# Server_CPU_Power.net
KiCad netlist of a schematic drawn in Altium Designer
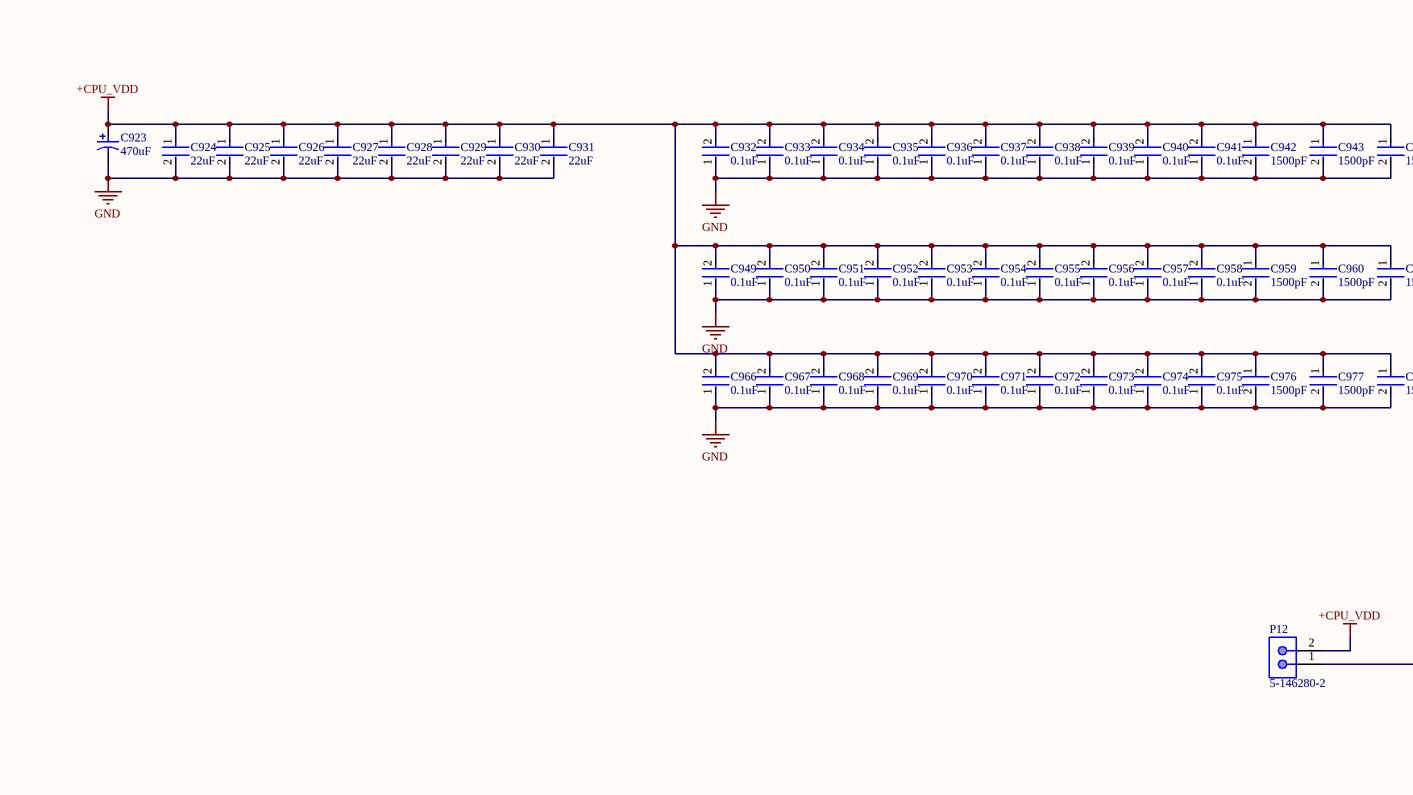
[diagram p0: Server_CPU_Power.SchDoc, top left]
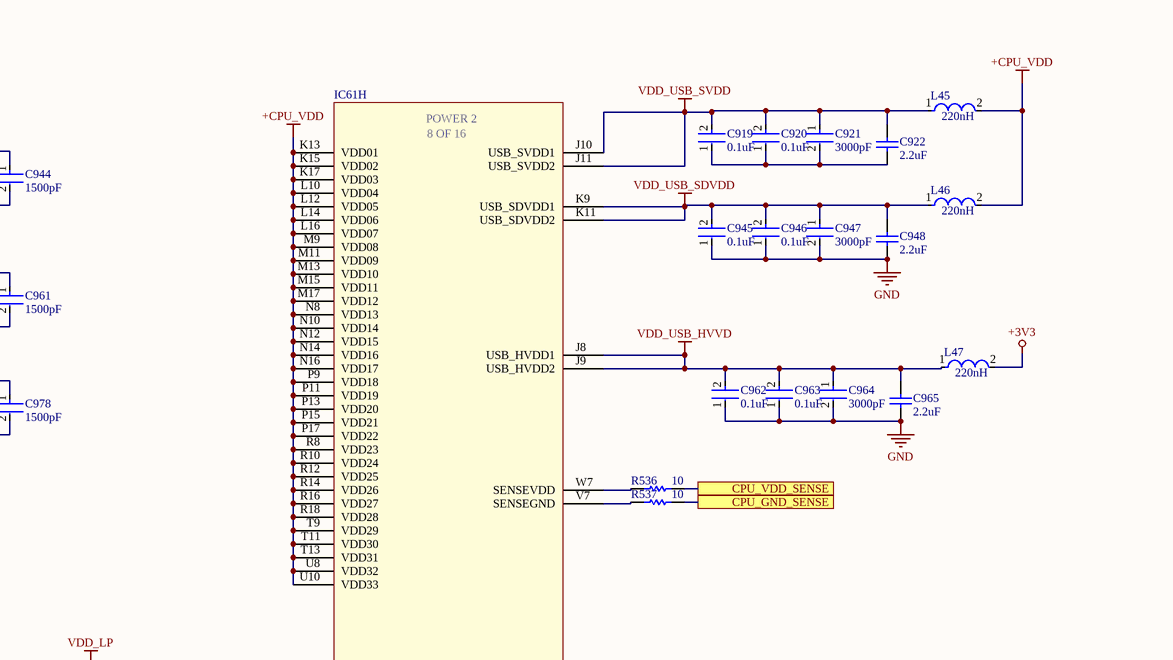
[diagram p1: Server_CPU_Power.SchDoc, top right]
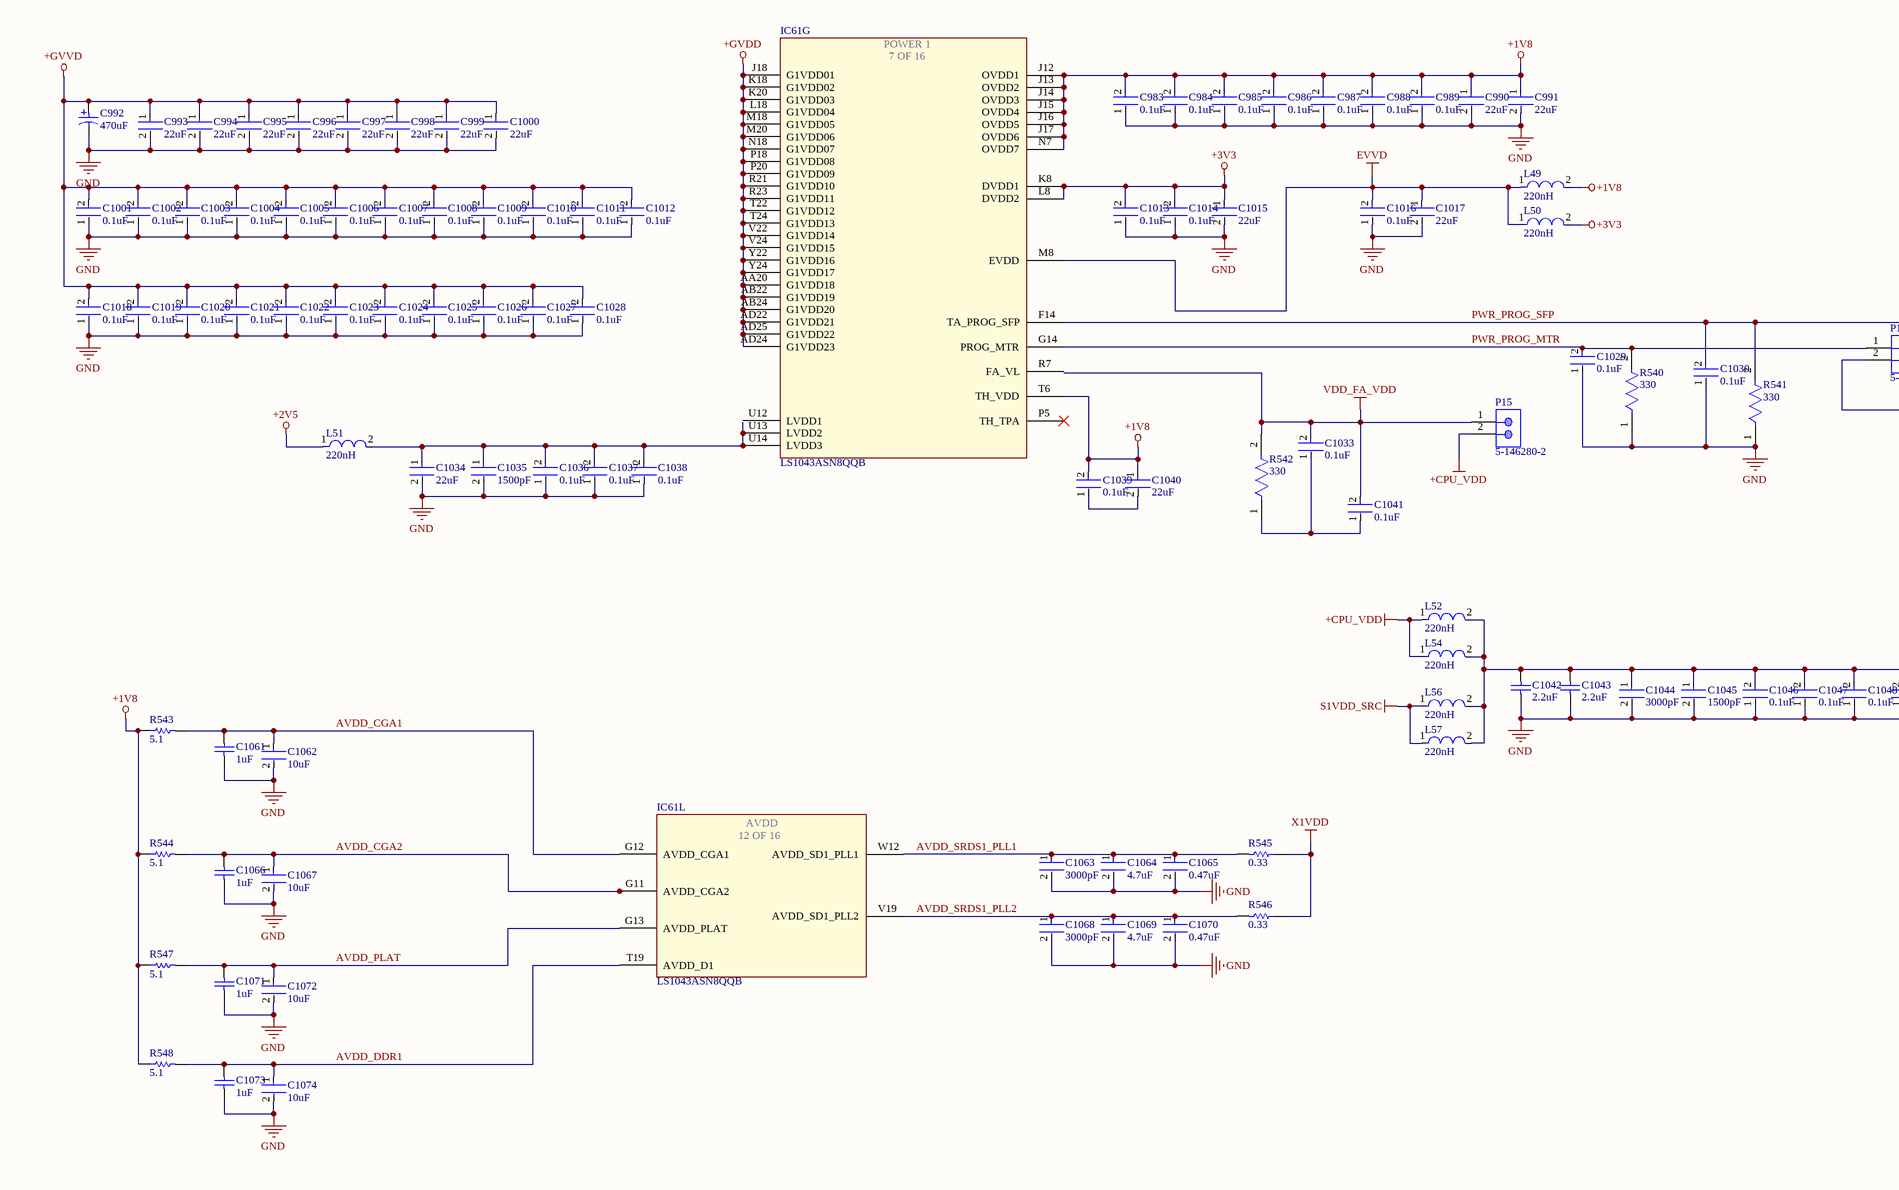
[diagram p2: Server_CPU_Power.SchDoc, bottom left]
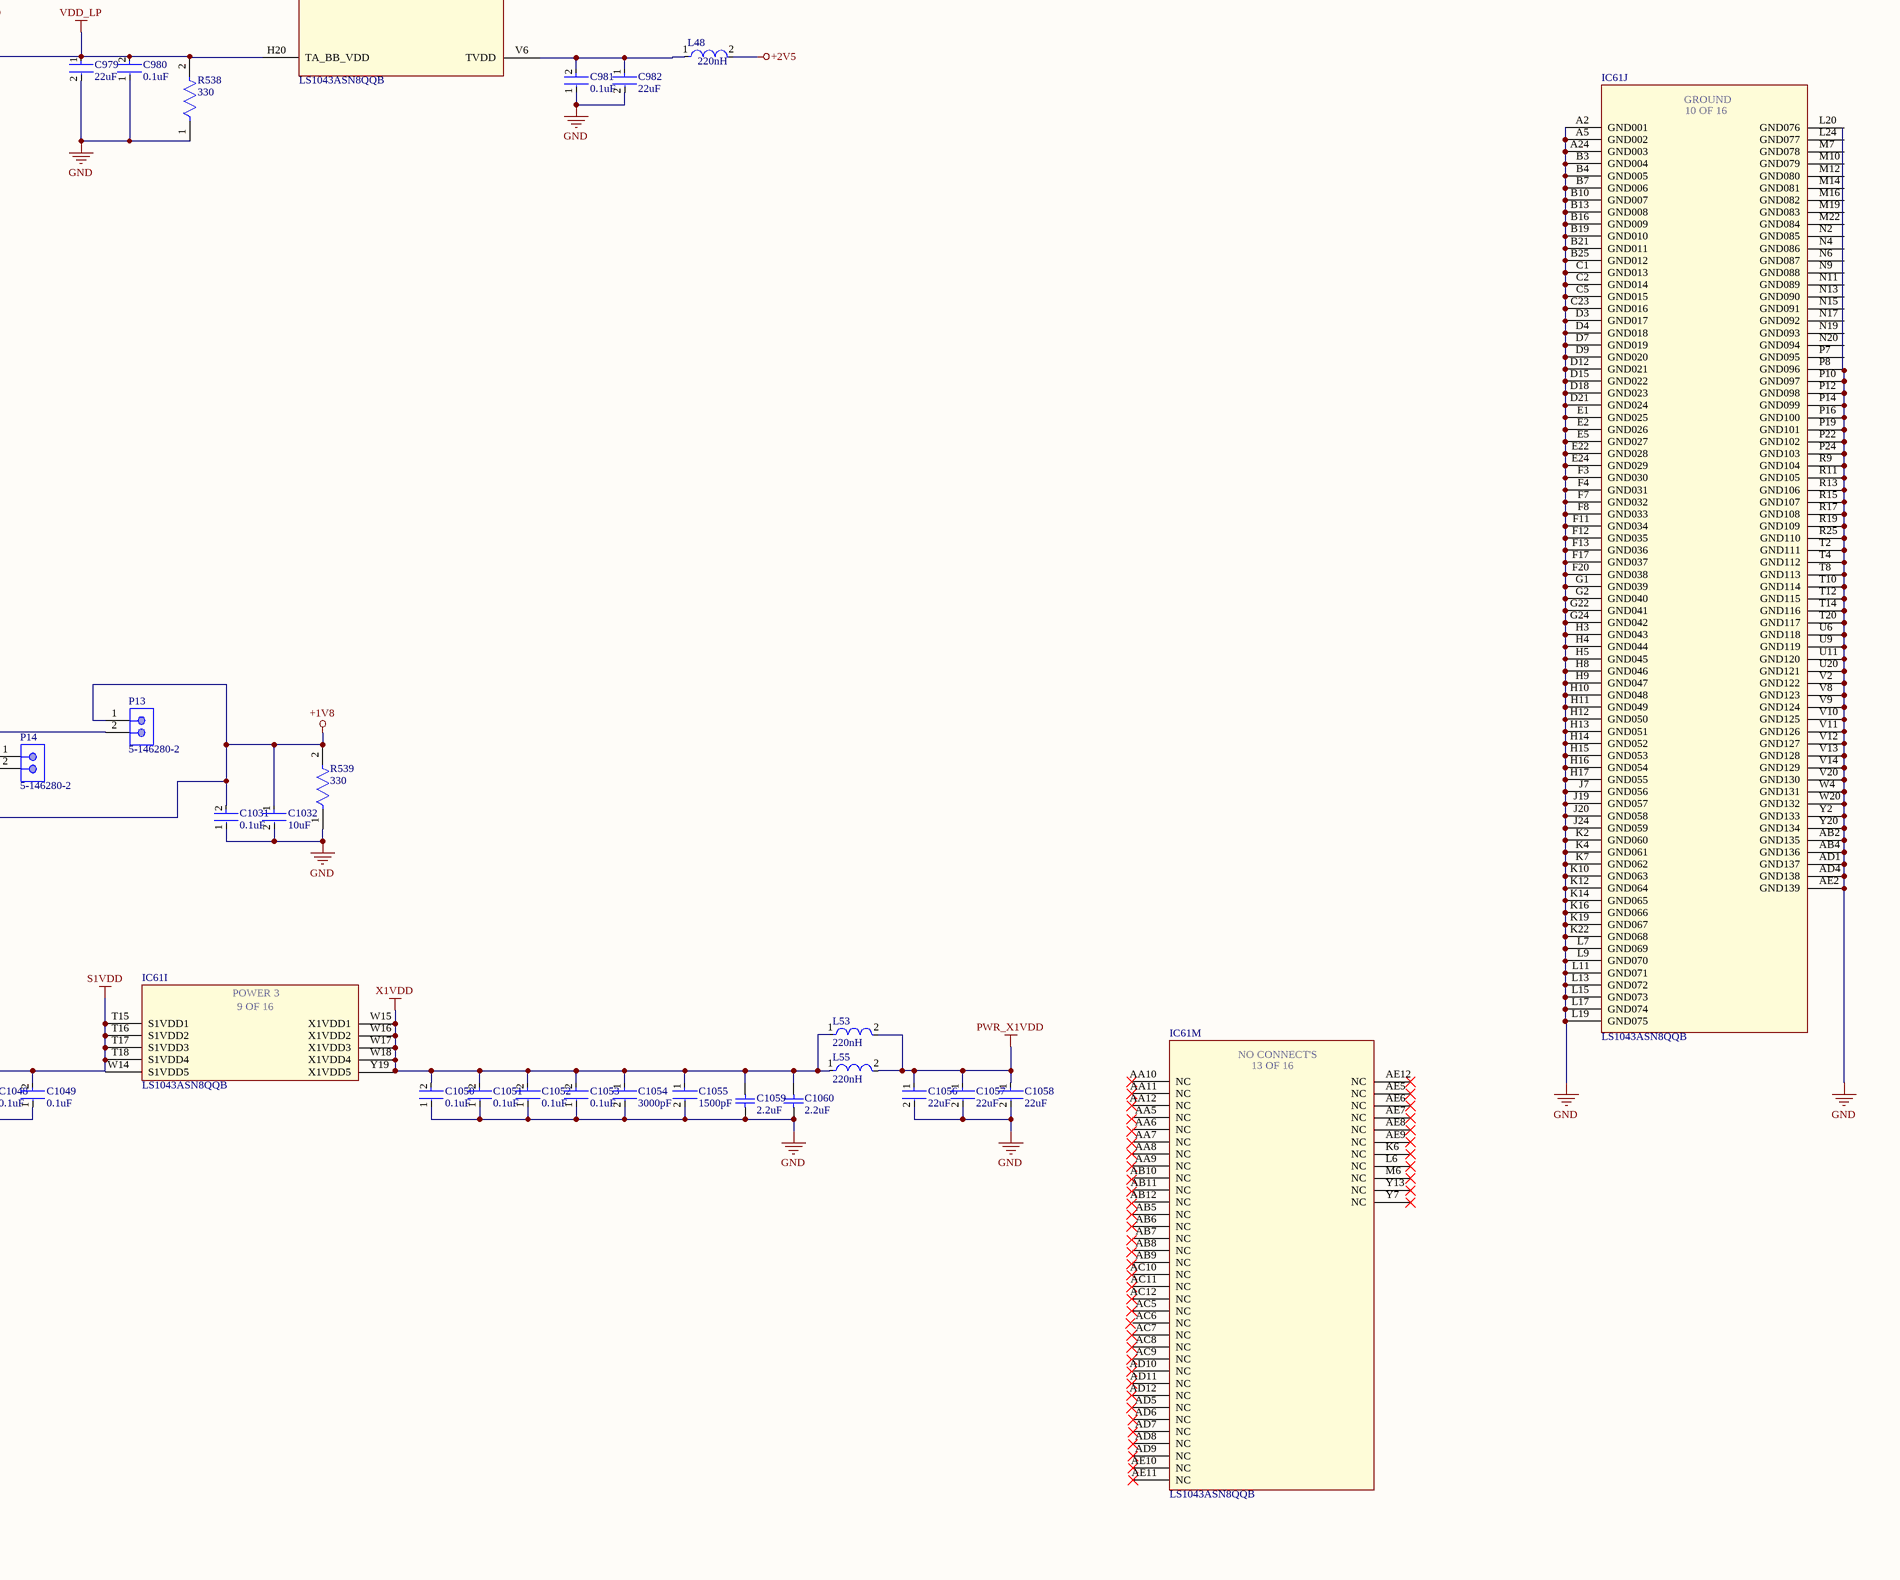
[diagram p3: Server_CPU_Power.SchDoc, bottom right]

(export (version "E")
  (design (tool "Eeschema 10.0.6"))
  (components
    (comp (ref "C919")
      (value "0.1uF")
      (footprint "FP-GRM15-MFG")
      (description "CAP CER 0.1UF 16V X7R 0402")
      (fields (field (name "MANUFACTURER PART NUMBER") "GRM155R71C104KA88D") (field (name "TOLERANCE") "10%"))
      (libsource (lib "Altium Content Vault") (part "236180d848d6139a670b325ea6854c9"))
    )
    (comp (ref "C920")
      (value "0.1uF")
      (footprint "FP-GRM15-MFG")
      (description "CAP CER 0.1UF 16V X7R 0402")
      (fields (field (name "MANUFACTURER PART NUMBER") "GRM155R71C104KA88D") (field (name "TOLERANCE") "10%"))
      (libsource (lib "Altium Content Vault") (part "236180d848d6139a670b325ea6854c9"))
    )
    (comp (ref "C921")
      (value "3000pF")
      (footprint "FP-GRM155-0_05-IPC_B")
      (description "Chip Multilayer Ceramic Capacitors for General Purpose, 0402, 3000pF, U2J, -750ppm/°C, 5%, 10V")
      (fields (field (name "TOLERANCE") "5%"))
      (libsource (lib "Altium Content Vault") (part "02cd4be3c70576c341d710602a673aa"))
    )
    (comp (ref "C922")
      (value "2.2uF")
      (footprint "CAPC1005X55X30NL05T10")
      (fields (field (name "MANUFACTURER") "Kemet") (field (name "PART NUMBER") "C0402C225M9PACTU"))
      (libsource (lib "Altium Content Vault") (part "CAP"))
    )
    (comp (ref "C923")
      (value "470uF")
      (footprint "PNSC-FK-V-F_V")
      (fields (field (name "MANUFACTURER") "Panasonic"))
      (libsource (lib "Altium Content Vault") (part "CAP-P-2"))
    )
    (comp (ref "C924")
      (value "22uF")
      (footprint "FP-GRM21B-0_15-MFG")
      (description "Chip Multilayer Ceramic Capacitors for General Purpose, 0805, 22uF, X5R, 15%, 20%, 6.3V")
      (fields (field (name "VOLTAGE") "6.3V") (field (name "TOLERANCE") "20%"))
      (libsource (lib "Altium Content Vault") (part "b4654b650e69147ec39a6b967a45e02"))
    )
    (comp (ref "C925")
      (value "22uF")
      (footprint "FP-GRM21B-0_15-MFG")
      (description "Chip Multilayer Ceramic Capacitors for General Purpose, 0805, 22uF, X5R, 15%, 20%, 6.3V")
      (fields (field (name "VOLTAGE") "6.3V") (field (name "TOLERANCE") "20%"))
      (libsource (lib "Altium Content Vault") (part "b4654b650e69147ec39a6b967a45e02"))
    )
    (comp (ref "C926")
      (value "22uF")
      (footprint "FP-GRM21B-0_15-MFG")
      (description "Chip Multilayer Ceramic Capacitors for General Purpose, 0805, 22uF, X5R, 15%, 20%, 6.3V")
      (fields (field (name "VOLTAGE") "6.3V") (field (name "TOLERANCE") "20%"))
      (libsource (lib "Altium Content Vault") (part "b4654b650e69147ec39a6b967a45e02"))
    )
    (comp (ref "C927")
      (value "22uF")
      (footprint "FP-GRM21B-0_15-MFG")
      (description "Chip Multilayer Ceramic Capacitors for General Purpose, 0805, 22uF, X5R, 15%, 20%, 6.3V")
      (fields (field (name "VOLTAGE") "6.3V") (field (name "TOLERANCE") "20%"))
      (libsource (lib "Altium Content Vault") (part "b4654b650e69147ec39a6b967a45e02"))
    )
    (comp (ref "C928")
      (value "22uF")
      (footprint "FP-GRM21B-0_15-MFG")
      (description "Chip Multilayer Ceramic Capacitors for General Purpose, 0805, 22uF, X5R, 15%, 20%, 6.3V")
      (fields (field (name "VOLTAGE") "6.3V") (field (name "TOLERANCE") "20%"))
      (libsource (lib "Altium Content Vault") (part "b4654b650e69147ec39a6b967a45e02"))
    )
    (comp (ref "C929")
      (value "22uF")
      (footprint "FP-GRM21B-0_15-MFG")
      (description "Chip Multilayer Ceramic Capacitors for General Purpose, 0805, 22uF, X5R, 15%, 20%, 6.3V")
      (fields (field (name "VOLTAGE") "6.3V") (field (name "TOLERANCE") "20%"))
      (libsource (lib "Altium Content Vault") (part "b4654b650e69147ec39a6b967a45e02"))
    )
    (comp (ref "C930")
      (value "22uF")
      (footprint "FP-GRM21B-0_15-MFG")
      (description "Chip Multilayer Ceramic Capacitors for General Purpose, 0805, 22uF, X5R, 15%, 20%, 6.3V")
      (fields (field (name "VOLTAGE") "6.3V") (field (name "TOLERANCE") "20%"))
      (libsource (lib "Altium Content Vault") (part "b4654b650e69147ec39a6b967a45e02"))
    )
    (comp (ref "C931")
      (value "22uF")
      (footprint "FP-GRM21B-0_15-MFG")
      (description "Chip Multilayer Ceramic Capacitors for General Purpose, 0805, 22uF, X5R, 15%, 20%, 6.3V")
      (fields (field (name "VOLTAGE") "6.3V") (field (name "TOLERANCE") "20%"))
      (libsource (lib "Altium Content Vault") (part "b4654b650e69147ec39a6b967a45e02"))
    )
    (comp (ref "C932")
      (value "0.1uF")
      (footprint "FP-GRM15-MFG")
      (description "CAP CER 0.1UF 16V X7R 0402")
      (fields (field (name "MANUFACTURER PART NUMBER") "GRM155R71C104KA88D") (field (name "TOLERANCE") "10%"))
      (libsource (lib "Altium Content Vault") (part "236180d848d6139a670b325ea6854c9"))
    )
    (comp (ref "C933")
      (value "0.1uF")
      (footprint "FP-GRM15-MFG")
      (description "CAP CER 0.1UF 16V X7R 0402")
      (fields (field (name "MANUFACTURER PART NUMBER") "GRM155R71C104KA88D") (field (name "TOLERANCE") "10%"))
      (libsource (lib "Altium Content Vault") (part "236180d848d6139a670b325ea6854c9"))
    )
    (comp (ref "C934")
      (value "0.1uF")
      (footprint "FP-GRM15-MFG")
      (description "CAP CER 0.1UF 16V X7R 0402")
      (fields (field (name "MANUFACTURER PART NUMBER") "GRM155R71C104KA88D") (field (name "TOLERANCE") "10%"))
      (libsource (lib "Altium Content Vault") (part "236180d848d6139a670b325ea6854c9"))
    )
    (comp (ref "C935")
      (value "0.1uF")
      (footprint "FP-GRM15-MFG")
      (description "CAP CER 0.1UF 16V X7R 0402")
      (fields (field (name "MANUFACTURER PART NUMBER") "GRM155R71C104KA88D") (field (name "TOLERANCE") "10%"))
      (libsource (lib "Altium Content Vault") (part "236180d848d6139a670b325ea6854c9"))
    )
    (comp (ref "C936")
      (value "0.1uF")
      (footprint "FP-GRM15-MFG")
      (description "CAP CER 0.1UF 16V X7R 0402")
      (fields (field (name "MANUFACTURER PART NUMBER") "GRM155R71C104KA88D") (field (name "TOLERANCE") "10%"))
      (libsource (lib "Altium Content Vault") (part "236180d848d6139a670b325ea6854c9"))
    )
    (comp (ref "C937")
      (value "0.1uF")
      (footprint "FP-GRM15-MFG")
      (description "CAP CER 0.1UF 16V X7R 0402")
      (fields (field (name "MANUFACTURER PART NUMBER") "GRM155R71C104KA88D") (field (name "TOLERANCE") "10%"))
      (libsource (lib "Altium Content Vault") (part "236180d848d6139a670b325ea6854c9"))
    )
    (comp (ref "C938")
      (value "0.1uF")
      (footprint "FP-GRM15-MFG")
      (description "CAP CER 0.1UF 16V X7R 0402")
      (fields (field (name "MANUFACTURER PART NUMBER") "GRM155R71C104KA88D") (field (name "TOLERANCE") "10%"))
      (libsource (lib "Altium Content Vault") (part "236180d848d6139a670b325ea6854c9"))
    )
    (comp (ref "C939")
      (value "0.1uF")
      (footprint "FP-GRM15-MFG")
      (description "CAP CER 0.1UF 16V X7R 0402")
      (fields (field (name "MANUFACTURER PART NUMBER") "GRM155R71C104KA88D") (field (name "TOLERANCE") "10%"))
      (libsource (lib "Altium Content Vault") (part "236180d848d6139a670b325ea6854c9"))
    )
    (comp (ref "C940")
      (value "0.1uF")
      (footprint "FP-GRM15-MFG")
      (description "CAP CER 0.1UF 16V X7R 0402")
      (fields (field (name "MANUFACTURER PART NUMBER") "GRM155R71C104KA88D") (field (name "TOLERANCE") "10%"))
      (libsource (lib "Altium Content Vault") (part "236180d848d6139a670b325ea6854c9"))
    )
    (comp (ref "C941")
      (value "0.1uF")
      (footprint "FP-GRM15-MFG")
      (description "CAP CER 0.1UF 16V X7R 0402")
      (fields (field (name "MANUFACTURER PART NUMBER") "GRM155R71C104KA88D") (field (name "TOLERANCE") "10%"))
      (libsource (lib "Altium Content Vault") (part "236180d848d6139a670b325ea6854c9"))
    )
    (comp (ref "C942")
      (value "1500pF")
      (footprint "FP-C0402-BB-MFG")
      (description "CAP CER 1500PF 50V X7R 0402")
      (fields
        (field (name "OCTOPART") "https://octopart.com/c0402c152k5ractu-kemet-125298")
        (field (name "TOLERANCE") "0.1")
      )
      (libsource (lib "Altium Content Vault") (part "b4654b650e69147ec39a6b967a45e02"))
    )
    (comp (ref "C943")
      (value "1500pF")
      (footprint "FP-C0402-BB-MFG")
      (description "CAP CER 1500PF 50V X7R 0402")
      (fields
        (field (name "OCTOPART") "https://octopart.com/c0402c152k5ractu-kemet-125298")
        (field (name "TOLERANCE") "0.1")
      )
      (libsource (lib "Altium Content Vault") (part "b4654b650e69147ec39a6b967a45e02"))
    )
    (comp (ref "C944")
      (value "1500pF")
      (footprint "FP-C0402-BB-MFG")
      (description "CAP CER 1500PF 50V X7R 0402")
      (fields
        (field (name "OCTOPART") "https://octopart.com/c0402c152k5ractu-kemet-125298")
        (field (name "TOLERANCE") "0.1")
      )
      (libsource (lib "Altium Content Vault") (part "b4654b650e69147ec39a6b967a45e02"))
    )
    (comp (ref "C945")
      (value "0.1uF")
      (footprint "FP-GRM15-MFG")
      (description "CAP CER 0.1UF 16V X7R 0402")
      (fields (field (name "MANUFACTURER PART NUMBER") "GRM155R71C104KA88D") (field (name "TOLERANCE") "10%"))
      (libsource (lib "Altium Content Vault") (part "236180d848d6139a670b325ea6854c9"))
    )
    (comp (ref "C946")
      (value "0.1uF")
      (footprint "FP-GRM15-MFG")
      (description "CAP CER 0.1UF 16V X7R 0402")
      (fields (field (name "MANUFACTURER PART NUMBER") "GRM155R71C104KA88D") (field (name "TOLERANCE") "10%"))
      (libsource (lib "Altium Content Vault") (part "236180d848d6139a670b325ea6854c9"))
    )
    (comp (ref "C947")
      (value "3000pF")
      (footprint "FP-GRM155-0_05-IPC_B")
      (description "Chip Multilayer Ceramic Capacitors for General Purpose, 0402, 3000pF, U2J, -750ppm/°C, 5%, 10V")
      (fields (field (name "TOLERANCE") "5%"))
      (libsource (lib "Altium Content Vault") (part "02cd4be3c70576c341d710602a673aa"))
    )
    (comp (ref "C948")
      (value "2.2uF")
      (footprint "CAPC1005X55X30NL05T10")
      (fields (field (name "MANUFACTURER") "Kemet") (field (name "PART NUMBER") "C0402C225M9PACTU"))
      (libsource (lib "Altium Content Vault") (part "CAP"))
    )
    (comp (ref "C949")
      (value "0.1uF")
      (footprint "FP-GRM15-MFG")
      (description "CAP CER 0.1UF 16V X7R 0402")
      (fields (field (name "MANUFACTURER PART NUMBER") "GRM155R71C104KA88D") (field (name "TOLERANCE") "10%"))
      (libsource (lib "Altium Content Vault") (part "236180d848d6139a670b325ea6854c9"))
    )
    (comp (ref "C950")
      (value "0.1uF")
      (footprint "FP-GRM15-MFG")
      (description "CAP CER 0.1UF 16V X7R 0402")
      (fields (field (name "MANUFACTURER PART NUMBER") "GRM155R71C104KA88D") (field (name "TOLERANCE") "10%"))
      (libsource (lib "Altium Content Vault") (part "236180d848d6139a670b325ea6854c9"))
    )
    (comp (ref "C951")
      (value "0.1uF")
      (footprint "FP-GRM15-MFG")
      (description "CAP CER 0.1UF 16V X7R 0402")
      (fields (field (name "MANUFACTURER PART NUMBER") "GRM155R71C104KA88D") (field (name "TOLERANCE") "10%"))
      (libsource (lib "Altium Content Vault") (part "236180d848d6139a670b325ea6854c9"))
    )
    (comp (ref "C952")
      (value "0.1uF")
      (footprint "FP-GRM15-MFG")
      (description "CAP CER 0.1UF 16V X7R 0402")
      (fields (field (name "MANUFACTURER PART NUMBER") "GRM155R71C104KA88D") (field (name "TOLERANCE") "10%"))
      (libsource (lib "Altium Content Vault") (part "236180d848d6139a670b325ea6854c9"))
    )
    (comp (ref "C953")
      (value "0.1uF")
      (footprint "FP-GRM15-MFG")
      (description "CAP CER 0.1UF 16V X7R 0402")
      (fields (field (name "MANUFACTURER PART NUMBER") "GRM155R71C104KA88D") (field (name "TOLERANCE") "10%"))
      (libsource (lib "Altium Content Vault") (part "236180d848d6139a670b325ea6854c9"))
    )
    (comp (ref "C954")
      (value "0.1uF")
      (footprint "FP-GRM15-MFG")
      (description "CAP CER 0.1UF 16V X7R 0402")
      (fields (field (name "MANUFACTURER PART NUMBER") "GRM155R71C104KA88D") (field (name "TOLERANCE") "10%"))
      (libsource (lib "Altium Content Vault") (part "236180d848d6139a670b325ea6854c9"))
    )
    (comp (ref "C955")
      (value "0.1uF")
      (footprint "FP-GRM15-MFG")
      (description "CAP CER 0.1UF 16V X7R 0402")
      (fields (field (name "MANUFACTURER PART NUMBER") "GRM155R71C104KA88D") (field (name "TOLERANCE") "10%"))
      (libsource (lib "Altium Content Vault") (part "236180d848d6139a670b325ea6854c9"))
    )
    (comp (ref "C956")
      (value "0.1uF")
      (footprint "FP-GRM15-MFG")
      (description "CAP CER 0.1UF 16V X7R 0402")
      (fields (field (name "MANUFACTURER PART NUMBER") "GRM155R71C104KA88D") (field (name "TOLERANCE") "10%"))
      (libsource (lib "Altium Content Vault") (part "236180d848d6139a670b325ea6854c9"))
    )
    (comp (ref "C957")
      (value "0.1uF")
      (footprint "FP-GRM15-MFG")
      (description "CAP CER 0.1UF 16V X7R 0402")
      (fields (field (name "MANUFACTURER PART NUMBER") "GRM155R71C104KA88D") (field (name "TOLERANCE") "10%"))
      (libsource (lib "Altium Content Vault") (part "236180d848d6139a670b325ea6854c9"))
    )
    (comp (ref "C958")
      (value "0.1uF")
      (footprint "FP-GRM15-MFG")
      (description "CAP CER 0.1UF 16V X7R 0402")
      (fields (field (name "MANUFACTURER PART NUMBER") "GRM155R71C104KA88D") (field (name "TOLERANCE") "10%"))
      (libsource (lib "Altium Content Vault") (part "236180d848d6139a670b325ea6854c9"))
    )
    (comp (ref "C959")
      (value "1500pF")
      (footprint "FP-C0402-BB-MFG")
      (description "CAP CER 1500PF 50V X7R 0402")
      (fields
        (field (name "OCTOPART") "https://octopart.com/c0402c152k5ractu-kemet-125298")
        (field (name "TOLERANCE") "0.1")
      )
      (libsource (lib "Altium Content Vault") (part "b4654b650e69147ec39a6b967a45e02"))
    )
    (comp (ref "C960")
      (value "1500pF")
      (footprint "FP-C0402-BB-MFG")
      (description "CAP CER 1500PF 50V X7R 0402")
      (fields
        (field (name "OCTOPART") "https://octopart.com/c0402c152k5ractu-kemet-125298")
        (field (name "TOLERANCE") "0.1")
      )
      (libsource (lib "Altium Content Vault") (part "b4654b650e69147ec39a6b967a45e02"))
    )
    (comp (ref "C961")
      (value "1500pF")
      (footprint "FP-C0402-BB-MFG")
      (description "CAP CER 1500PF 50V X7R 0402")
      (fields
        (field (name "OCTOPART") "https://octopart.com/c0402c152k5ractu-kemet-125298")
        (field (name "TOLERANCE") "0.1")
      )
      (libsource (lib "Altium Content Vault") (part "b4654b650e69147ec39a6b967a45e02"))
    )
    (comp (ref "C962")
      (value "0.1uF")
      (footprint "FP-GRM15-MFG")
      (description "CAP CER 0.1UF 16V X7R 0402")
      (fields (field (name "MANUFACTURER PART NUMBER") "GRM155R71C104KA88D") (field (name "TOLERANCE") "10%"))
      (libsource (lib "Altium Content Vault") (part "236180d848d6139a670b325ea6854c9"))
    )
    (comp (ref "C963")
      (value "0.1uF")
      (footprint "FP-GRM15-MFG")
      (description "CAP CER 0.1UF 16V X7R 0402")
      (fields (field (name "MANUFACTURER PART NUMBER") "GRM155R71C104KA88D") (field (name "TOLERANCE") "10%"))
      (libsource (lib "Altium Content Vault") (part "236180d848d6139a670b325ea6854c9"))
    )
    (comp (ref "C964")
      (value "3000pF")
      (footprint "FP-GRM155-0_05-IPC_B")
      (description "Chip Multilayer Ceramic Capacitors for General Purpose, 0402, 3000pF, U2J, -750ppm/°C, 5%, 10V")
      (fields (field (name "TOLERANCE") "5%"))
      (libsource (lib "Altium Content Vault") (part "02cd4be3c70576c341d710602a673aa"))
    )
    (comp (ref "C965")
      (value "2.2uF")
      (footprint "CAPC1005X55X30NL05T10")
      (fields (field (name "MANUFACTURER") "Kemet") (field (name "PART NUMBER") "C0402C225M9PACTU"))
      (libsource (lib "Altium Content Vault") (part "CAP"))
    )
    (comp (ref "C966")
      (value "0.1uF")
      (footprint "FP-GRM15-MFG")
      (description "CAP CER 0.1UF 16V X7R 0402")
      (fields (field (name "MANUFACTURER PART NUMBER") "GRM155R71C104KA88D") (field (name "TOLERANCE") "10%"))
      (libsource (lib "Altium Content Vault") (part "236180d848d6139a670b325ea6854c9"))
    )
    (comp (ref "C967")
      (value "0.1uF")
      (footprint "FP-GRM15-MFG")
      (description "CAP CER 0.1UF 16V X7R 0402")
      (fields (field (name "MANUFACTURER PART NUMBER") "GRM155R71C104KA88D") (field (name "TOLERANCE") "10%"))
      (libsource (lib "Altium Content Vault") (part "236180d848d6139a670b325ea6854c9"))
    )
    (comp (ref "C968")
      (value "0.1uF")
      (footprint "FP-GRM15-MFG")
      (description "CAP CER 0.1UF 16V X7R 0402")
      (fields (field (name "MANUFACTURER PART NUMBER") "GRM155R71C104KA88D") (field (name "TOLERANCE") "10%"))
      (libsource (lib "Altium Content Vault") (part "236180d848d6139a670b325ea6854c9"))
    )
    (comp (ref "C969")
      (value "0.1uF")
      (footprint "FP-GRM15-MFG")
      (description "CAP CER 0.1UF 16V X7R 0402")
      (fields (field (name "MANUFACTURER PART NUMBER") "GRM155R71C104KA88D") (field (name "TOLERANCE") "10%"))
      (libsource (lib "Altium Content Vault") (part "236180d848d6139a670b325ea6854c9"))
    )
    (comp (ref "C970")
      (value "0.1uF")
      (footprint "FP-GRM15-MFG")
      (description "CAP CER 0.1UF 16V X7R 0402")
      (fields (field (name "MANUFACTURER PART NUMBER") "GRM155R71C104KA88D") (field (name "TOLERANCE") "10%"))
      (libsource (lib "Altium Content Vault") (part "236180d848d6139a670b325ea6854c9"))
    )
    (comp (ref "C971")
      (value "0.1uF")
      (footprint "FP-GRM15-MFG")
      (description "CAP CER 0.1UF 16V X7R 0402")
      (fields (field (name "MANUFACTURER PART NUMBER") "GRM155R71C104KA88D") (field (name "TOLERANCE") "10%"))
      (libsource (lib "Altium Content Vault") (part "236180d848d6139a670b325ea6854c9"))
    )
    (comp (ref "C972")
      (value "0.1uF")
      (footprint "FP-GRM15-MFG")
      (description "CAP CER 0.1UF 16V X7R 0402")
      (fields (field (name "MANUFACTURER PART NUMBER") "GRM155R71C104KA88D") (field (name "TOLERANCE") "10%"))
      (libsource (lib "Altium Content Vault") (part "236180d848d6139a670b325ea6854c9"))
    )
    (comp (ref "C973")
      (value "0.1uF")
      (footprint "FP-GRM15-MFG")
      (description "CAP CER 0.1UF 16V X7R 0402")
      (fields (field (name "MANUFACTURER PART NUMBER") "GRM155R71C104KA88D") (field (name "TOLERANCE") "10%"))
      (libsource (lib "Altium Content Vault") (part "236180d848d6139a670b325ea6854c9"))
    )
    (comp (ref "C974")
      (value "0.1uF")
      (footprint "FP-GRM15-MFG")
      (description "CAP CER 0.1UF 16V X7R 0402")
      (fields (field (name "MANUFACTURER PART NUMBER") "GRM155R71C104KA88D") (field (name "TOLERANCE") "10%"))
      (libsource (lib "Altium Content Vault") (part "236180d848d6139a670b325ea6854c9"))
    )
    (comp (ref "C975")
      (value "0.1uF")
      (footprint "FP-GRM15-MFG")
      (description "CAP CER 0.1UF 16V X7R 0402")
      (fields (field (name "MANUFACTURER PART NUMBER") "GRM155R71C104KA88D") (field (name "TOLERANCE") "10%"))
      (libsource (lib "Altium Content Vault") (part "236180d848d6139a670b325ea6854c9"))
    )
    (comp (ref "C976")
      (value "1500pF")
      (footprint "FP-C0402-BB-MFG")
      (description "CAP CER 1500PF 50V X7R 0402")
      (fields
        (field (name "OCTOPART") "https://octopart.com/c0402c152k5ractu-kemet-125298")
        (field (name "TOLERANCE") "0.1")
      )
      (libsource (lib "Altium Content Vault") (part "b4654b650e69147ec39a6b967a45e02"))
    )
    (comp (ref "C977")
      (value "1500pF")
      (footprint "FP-C0402-BB-MFG")
      (description "CAP CER 1500PF 50V X7R 0402")
      (fields
        (field (name "OCTOPART") "https://octopart.com/c0402c152k5ractu-kemet-125298")
        (field (name "TOLERANCE") "0.1")
      )
      (libsource (lib "Altium Content Vault") (part "b4654b650e69147ec39a6b967a45e02"))
    )
    (comp (ref "C978")
      (value "1500pF")
      (footprint "FP-C0402-BB-MFG")
      (description "CAP CER 1500PF 50V X7R 0402")
      (fields
        (field (name "OCTOPART") "https://octopart.com/c0402c152k5ractu-kemet-125298")
        (field (name "TOLERANCE") "0.1")
      )
      (libsource (lib "Altium Content Vault") (part "b4654b650e69147ec39a6b967a45e02"))
    )
    (comp (ref "C979")
      (value "22uF")
      (footprint "FP-GRM21B-0_15-MFG")
      (description "Chip Multilayer Ceramic Capacitors for General Purpose, 0805, 22uF, X5R, 15%, 20%, 6.3V")
      (fields (field (name "VOLTAGE") "6.3V") (field (name "TOLERANCE") "20%"))
      (libsource (lib "Altium Content Vault") (part "b4654b650e69147ec39a6b967a45e02"))
    )
    (comp (ref "C980")
      (value "0.1uF")
      (footprint "FP-GRM15-MFG")
      (description "CAP CER 0.1UF 16V X7R 0402")
      (fields (field (name "MANUFACTURER PART NUMBER") "GRM155R71C104KA88D") (field (name "TOLERANCE") "10%"))
      (libsource (lib "Altium Content Vault") (part "236180d848d6139a670b325ea6854c9"))
    )
    (comp (ref "C981")
      (value "0.1uF")
      (footprint "FP-GRM15-MFG")
      (description "CAP CER 0.1UF 16V X7R 0402")
      (fields (field (name "MANUFACTURER PART NUMBER") "GRM155R71C104KA88D") (field (name "TOLERANCE") "10%"))
      (libsource (lib "Altium Content Vault") (part "236180d848d6139a670b325ea6854c9"))
    )
    (comp (ref "C982")
      (value "22uF")
      (footprint "FP-GRM21B-0_15-MFG")
      (description "Chip Multilayer Ceramic Capacitors for General Purpose, 0805, 22uF, X5R, 15%, 20%, 6.3V")
      (fields (field (name "VOLTAGE") "6.3V") (field (name "TOLERANCE") "20%"))
      (libsource (lib "Altium Content Vault") (part "b4654b650e69147ec39a6b967a45e02"))
    )
    (comp (ref "C983")
      (value "0.1uF")
      (footprint "FP-GRM15-MFG")
      (description "CAP CER 0.1UF 16V X7R 0402")
      (fields (field (name "MANUFACTURER PART NUMBER") "GRM155R71C104KA88D") (field (name "TOLERANCE") "10%"))
      (libsource (lib "Altium Content Vault") (part "236180d848d6139a670b325ea6854c9"))
    )
    (comp (ref "C984")
      (value "0.1uF")
      (footprint "FP-GRM15-MFG")
      (description "CAP CER 0.1UF 16V X7R 0402")
      (fields (field (name "MANUFACTURER PART NUMBER") "GRM155R71C104KA88D") (field (name "TOLERANCE") "10%"))
      (libsource (lib "Altium Content Vault") (part "236180d848d6139a670b325ea6854c9"))
    )
    (comp (ref "C985")
      (value "0.1uF")
      (footprint "FP-GRM15-MFG")
      (description "CAP CER 0.1UF 16V X7R 0402")
      (fields (field (name "MANUFACTURER PART NUMBER") "GRM155R71C104KA88D") (field (name "TOLERANCE") "10%"))
      (libsource (lib "Altium Content Vault") (part "236180d848d6139a670b325ea6854c9"))
    )
    (comp (ref "C986")
      (value "0.1uF")
      (footprint "FP-GRM15-MFG")
      (description "CAP CER 0.1UF 16V X7R 0402")
      (fields (field (name "MANUFACTURER PART NUMBER") "GRM155R71C104KA88D") (field (name "TOLERANCE") "10%"))
      (libsource (lib "Altium Content Vault") (part "236180d848d6139a670b325ea6854c9"))
    )
    (comp (ref "C987")
      (value "0.1uF")
      (footprint "FP-GRM15-MFG")
      (description "CAP CER 0.1UF 16V X7R 0402")
      (fields (field (name "MANUFACTURER PART NUMBER") "GRM155R71C104KA88D") (field (name "TOLERANCE") "10%"))
      (libsource (lib "Altium Content Vault") (part "236180d848d6139a670b325ea6854c9"))
    )
    (comp (ref "C988")
      (value "0.1uF")
      (footprint "FP-GRM15-MFG")
      (description "CAP CER 0.1UF 16V X7R 0402")
      (fields (field (name "MANUFACTURER PART NUMBER") "GRM155R71C104KA88D") (field (name "TOLERANCE") "10%"))
      (libsource (lib "Altium Content Vault") (part "236180d848d6139a670b325ea6854c9"))
    )
    (comp (ref "C989")
      (value "0.1uF")
      (footprint "FP-GRM15-MFG")
      (description "CAP CER 0.1UF 16V X7R 0402")
      (fields (field (name "MANUFACTURER PART NUMBER") "GRM155R71C104KA88D") (field (name "TOLERANCE") "10%"))
      (libsource (lib "Altium Content Vault") (part "236180d848d6139a670b325ea6854c9"))
    )
    (comp (ref "C990")
      (value "22uF")
      (footprint "FP-GRM21B-0_15-MFG")
      (description "Chip Multilayer Ceramic Capacitors for General Purpose, 0805, 22uF, X5R, 15%, 20%, 6.3V")
      (fields (field (name "VOLTAGE") "6.3V") (field (name "TOLERANCE") "20%"))
      (libsource (lib "Altium Content Vault") (part "b4654b650e69147ec39a6b967a45e02"))
    )
    (comp (ref "C991")
      (value "22uF")
      (footprint "FP-GRM21B-0_15-MFG")
      (description "Chip Multilayer Ceramic Capacitors for General Purpose, 0805, 22uF, X5R, 15%, 20%, 6.3V")
      (fields (field (name "VOLTAGE") "6.3V") (field (name "TOLERANCE") "20%"))
      (libsource (lib "Altium Content Vault") (part "b4654b650e69147ec39a6b967a45e02"))
    )
    (comp (ref "C992")
      (value "470uF")
      (footprint "PNSC-FK-V-F_V")
      (fields (field (name "MANUFACTURER") "Panasonic"))
      (libsource (lib "Altium Content Vault") (part "CAP-P-2"))
    )
    (comp (ref "C993")
      (value "22uF")
      (footprint "FP-GRM21B-0_15-MFG")
      (description "Chip Multilayer Ceramic Capacitors for General Purpose, 0805, 22uF, X5R, 15%, 20%, 6.3V")
      (fields (field (name "VOLTAGE") "6.3V") (field (name "TOLERANCE") "20%"))
      (libsource (lib "Altium Content Vault") (part "b4654b650e69147ec39a6b967a45e02"))
    )
    (comp (ref "C994")
      (value "22uF")
      (footprint "FP-GRM21B-0_15-MFG")
      (description "Chip Multilayer Ceramic Capacitors for General Purpose, 0805, 22uF, X5R, 15%, 20%, 6.3V")
      (fields (field (name "VOLTAGE") "6.3V") (field (name "TOLERANCE") "20%"))
      (libsource (lib "Altium Content Vault") (part "b4654b650e69147ec39a6b967a45e02"))
    )
    (comp (ref "C995")
      (value "22uF")
      (footprint "FP-GRM21B-0_15-MFG")
      (description "Chip Multilayer Ceramic Capacitors for General Purpose, 0805, 22uF, X5R, 15%, 20%, 6.3V")
      (fields (field (name "VOLTAGE") "6.3V") (field (name "TOLERANCE") "20%"))
      (libsource (lib "Altium Content Vault") (part "b4654b650e69147ec39a6b967a45e02"))
    )
    (comp (ref "C996")
      (value "22uF")
      (footprint "FP-GRM21B-0_15-MFG")
      (description "Chip Multilayer Ceramic Capacitors for General Purpose, 0805, 22uF, X5R, 15%, 20%, 6.3V")
      (fields (field (name "VOLTAGE") "6.3V") (field (name "TOLERANCE") "20%"))
      (libsource (lib "Altium Content Vault") (part "b4654b650e69147ec39a6b967a45e02"))
    )
    (comp (ref "C997")
      (value "22uF")
      (footprint "FP-GRM21B-0_15-MFG")
      (description "Chip Multilayer Ceramic Capacitors for General Purpose, 0805, 22uF, X5R, 15%, 20%, 6.3V")
      (fields (field (name "VOLTAGE") "6.3V") (field (name "TOLERANCE") "20%"))
      (libsource (lib "Altium Content Vault") (part "b4654b650e69147ec39a6b967a45e02"))
    )
    (comp (ref "C998")
      (value "22uF")
      (footprint "FP-GRM21B-0_15-MFG")
      (description "Chip Multilayer Ceramic Capacitors for General Purpose, 0805, 22uF, X5R, 15%, 20%, 6.3V")
      (fields (field (name "VOLTAGE") "6.3V") (field (name "TOLERANCE") "20%"))
      (libsource (lib "Altium Content Vault") (part "b4654b650e69147ec39a6b967a45e02"))
    )
    (comp (ref "C999")
      (value "22uF")
      (footprint "FP-GRM21B-0_15-MFG")
      (description "Chip Multilayer Ceramic Capacitors for General Purpose, 0805, 22uF, X5R, 15%, 20%, 6.3V")
      (fields (field (name "VOLTAGE") "6.3V") (field (name "TOLERANCE") "20%"))
      (libsource (lib "Altium Content Vault") (part "b4654b650e69147ec39a6b967a45e02"))
    )
    (comp (ref "C1000")
      (value "22uF")
      (footprint "FP-GRM21B-0_15-MFG")
      (description "Chip Multilayer Ceramic Capacitors for General Purpose, 0805, 22uF, X5R, 15%, 20%, 6.3V")
      (fields (field (name "VOLTAGE") "6.3V") (field (name "TOLERANCE") "20%"))
      (libsource (lib "Altium Content Vault") (part "b4654b650e69147ec39a6b967a45e02"))
    )
    (comp (ref "C1001")
      (value "0.1uF")
      (footprint "FP-GRM15-MFG")
      (description "CAP CER 0.1UF 16V X7R 0402")
      (fields (field (name "MANUFACTURER PART NUMBER") "GRM155R71C104KA88D") (field (name "TOLERANCE") "10%"))
      (libsource (lib "Altium Content Vault") (part "236180d848d6139a670b325ea6854c9"))
    )
    (comp (ref "C1002")
      (value "0.1uF")
      (footprint "FP-GRM15-MFG")
      (description "CAP CER 0.1UF 16V X7R 0402")
      (fields (field (name "MANUFACTURER PART NUMBER") "GRM155R71C104KA88D") (field (name "TOLERANCE") "10%"))
      (libsource (lib "Altium Content Vault") (part "236180d848d6139a670b325ea6854c9"))
    )
    (comp (ref "C1003")
      (value "0.1uF")
      (footprint "FP-GRM15-MFG")
      (description "CAP CER 0.1UF 16V X7R 0402")
      (fields (field (name "MANUFACTURER PART NUMBER") "GRM155R71C104KA88D") (field (name "TOLERANCE") "10%"))
      (libsource (lib "Altium Content Vault") (part "236180d848d6139a670b325ea6854c9"))
    )
    (comp (ref "C1004")
      (value "0.1uF")
      (footprint "FP-GRM15-MFG")
      (description "CAP CER 0.1UF 16V X7R 0402")
      (fields (field (name "MANUFACTURER PART NUMBER") "GRM155R71C104KA88D") (field (name "TOLERANCE") "10%"))
      (libsource (lib "Altium Content Vault") (part "236180d848d6139a670b325ea6854c9"))
    )
    (comp (ref "C1005")
      (value "0.1uF")
      (footprint "FP-GRM15-MFG")
      (description "CAP CER 0.1UF 16V X7R 0402")
      (fields (field (name "MANUFACTURER PART NUMBER") "GRM155R71C104KA88D") (field (name "TOLERANCE") "10%"))
      (libsource (lib "Altium Content Vault") (part "236180d848d6139a670b325ea6854c9"))
    )
    (comp (ref "C1006")
      (value "0.1uF")
      (footprint "FP-GRM15-MFG")
      (description "CAP CER 0.1UF 16V X7R 0402")
      (fields (field (name "MANUFACTURER PART NUMBER") "GRM155R71C104KA88D") (field (name "TOLERANCE") "10%"))
      (libsource (lib "Altium Content Vault") (part "236180d848d6139a670b325ea6854c9"))
    )
    (comp (ref "C1007")
      (value "0.1uF")
      (footprint "FP-GRM15-MFG")
      (description "CAP CER 0.1UF 16V X7R 0402")
      (fields (field (name "MANUFACTURER PART NUMBER") "GRM155R71C104KA88D") (field (name "TOLERANCE") "10%"))
      (libsource (lib "Altium Content Vault") (part "236180d848d6139a670b325ea6854c9"))
    )
    (comp (ref "C1008")
      (value "0.1uF")
      (footprint "FP-GRM15-MFG")
      (description "CAP CER 0.1UF 16V X7R 0402")
      (fields (field (name "MANUFACTURER PART NUMBER") "GRM155R71C104KA88D") (field (name "TOLERANCE") "10%"))
      (libsource (lib "Altium Content Vault") (part "236180d848d6139a670b325ea6854c9"))
    )
    (comp (ref "C1009")
      (value "0.1uF")
      (footprint "FP-GRM15-MFG")
      (description "CAP CER 0.1UF 16V X7R 0402")
      (fields (field (name "MANUFACTURER PART NUMBER") "GRM155R71C104KA88D") (field (name "TOLERANCE") "10%"))
      (libsource (lib "Altium Content Vault") (part "236180d848d6139a670b325ea6854c9"))
    )
    (comp (ref "C1010")
      (value "0.1uF")
      (footprint "FP-GRM15-MFG")
      (description "CAP CER 0.1UF 16V X7R 0402")
      (fields (field (name "MANUFACTURER PART NUMBER") "GRM155R71C104KA88D") (field (name "TOLERANCE") "10%"))
      (libsource (lib "Altium Content Vault") (part "236180d848d6139a670b325ea6854c9"))
    )
    (comp (ref "C1011")
      (value "0.1uF")
      (footprint "FP-GRM15-MFG")
      (description "CAP CER 0.1UF 16V X7R 0402")
      (fields (field (name "MANUFACTURER PART NUMBER") "GRM155R71C104KA88D") (field (name "TOLERANCE") "10%"))
      (libsource (lib "Altium Content Vault") (part "236180d848d6139a670b325ea6854c9"))
    )
    (comp (ref "C1012")
      (value "0.1uF")
      (footprint "FP-GRM15-MFG")
      (description "CAP CER 0.1UF 16V X7R 0402")
      (fields (field (name "MANUFACTURER PART NUMBER") "GRM155R71C104KA88D") (field (name "TOLERANCE") "10%"))
      (libsource (lib "Altium Content Vault") (part "236180d848d6139a670b325ea6854c9"))
    )
    (comp (ref "C1013")
      (value "0.1uF")
      (footprint "FP-GRM15-MFG")
      (description "CAP CER 0.1UF 16V X7R 0402")
      (fields (field (name "MANUFACTURER PART NUMBER") "GRM155R71C104KA88D") (field (name "TOLERANCE") "10%"))
      (libsource (lib "Altium Content Vault") (part "236180d848d6139a670b325ea6854c9"))
    )
    (comp (ref "C1014")
      (value "0.1uF")
      (footprint "FP-GRM15-MFG")
      (description "CAP CER 0.1UF 16V X7R 0402")
      (fields (field (name "MANUFACTURER PART NUMBER") "GRM155R71C104KA88D") (field (name "TOLERANCE") "10%"))
      (libsource (lib "Altium Content Vault") (part "236180d848d6139a670b325ea6854c9"))
    )
    (comp (ref "C1015")
      (value "22uF")
      (footprint "FP-GRM21B-0_15-MFG")
      (description "Chip Multilayer Ceramic Capacitors for General Purpose, 0805, 22uF, X5R, 15%, 20%, 6.3V")
      (fields (field (name "VOLTAGE") "6.3V") (field (name "TOLERANCE") "20%"))
      (libsource (lib "Altium Content Vault") (part "b4654b650e69147ec39a6b967a45e02"))
    )
    (comp (ref "C1016")
      (value "0.1uF")
      (footprint "FP-GRM15-MFG")
      (description "CAP CER 0.1UF 16V X7R 0402")
      (fields (field (name "MANUFACTURER PART NUMBER") "GRM155R71C104KA88D") (field (name "TOLERANCE") "10%"))
      (libsource (lib "Altium Content Vault") (part "236180d848d6139a670b325ea6854c9"))
    )
    (comp (ref "C1017")
      (value "22uF")
      (footprint "FP-GRM21B-0_15-MFG")
      (description "Chip Multilayer Ceramic Capacitors for General Purpose, 0805, 22uF, X5R, 15%, 20%, 6.3V")
      (fields (field (name "VOLTAGE") "6.3V") (field (name "TOLERANCE") "20%"))
      (libsource (lib "Altium Content Vault") (part "b4654b650e69147ec39a6b967a45e02"))
    )
    (comp (ref "C1018")
      (value "0.1uF")
      (footprint "FP-GRM15-MFG")
      (description "CAP CER 0.1UF 16V X7R 0402")
      (fields (field (name "MANUFACTURER PART NUMBER") "GRM155R71C104KA88D") (field (name "TOLERANCE") "10%"))
      (libsource (lib "Altium Content Vault") (part "236180d848d6139a670b325ea6854c9"))
    )
    (comp (ref "C1019")
      (value "0.1uF")
      (footprint "FP-GRM15-MFG")
      (description "CAP CER 0.1UF 16V X7R 0402")
      (fields (field (name "MANUFACTURER PART NUMBER") "GRM155R71C104KA88D") (field (name "TOLERANCE") "10%"))
      (libsource (lib "Altium Content Vault") (part "236180d848d6139a670b325ea6854c9"))
    )
    (comp (ref "C1020")
      (value "0.1uF")
      (footprint "FP-GRM15-MFG")
      (description "CAP CER 0.1UF 16V X7R 0402")
      (fields (field (name "MANUFACTURER PART NUMBER") "GRM155R71C104KA88D") (field (name "TOLERANCE") "10%"))
      (libsource (lib "Altium Content Vault") (part "236180d848d6139a670b325ea6854c9"))
    )
    (comp (ref "C1021")
      (value "0.1uF")
      (footprint "FP-GRM15-MFG")
      (description "CAP CER 0.1UF 16V X7R 0402")
      (fields (field (name "MANUFACTURER PART NUMBER") "GRM155R71C104KA88D") (field (name "TOLERANCE") "10%"))
      (libsource (lib "Altium Content Vault") (part "236180d848d6139a670b325ea6854c9"))
    )
    (comp (ref "C1022")
      (value "0.1uF")
      (footprint "FP-GRM15-MFG")
      (description "CAP CER 0.1UF 16V X7R 0402")
      (fields (field (name "MANUFACTURER PART NUMBER") "GRM155R71C104KA88D") (field (name "TOLERANCE") "10%"))
      (libsource (lib "Altium Content Vault") (part "236180d848d6139a670b325ea6854c9"))
    )
    (comp (ref "C1023")
      (value "0.1uF")
      (footprint "FP-GRM15-MFG")
      (description "CAP CER 0.1UF 16V X7R 0402")
      (fields (field (name "MANUFACTURER PART NUMBER") "GRM155R71C104KA88D") (field (name "TOLERANCE") "10%"))
      (libsource (lib "Altium Content Vault") (part "236180d848d6139a670b325ea6854c9"))
    )
    (comp (ref "C1024")
      (value "0.1uF")
      (footprint "FP-GRM15-MFG")
      (description "CAP CER 0.1UF 16V X7R 0402")
      (fields (field (name "MANUFACTURER PART NUMBER") "GRM155R71C104KA88D") (field (name "TOLERANCE") "10%"))
      (libsource (lib "Altium Content Vault") (part "236180d848d6139a670b325ea6854c9"))
    )
    (comp (ref "C1025")
      (value "0.1uF")
      (footprint "FP-GRM15-MFG")
      (description "CAP CER 0.1UF 16V X7R 0402")
      (fields (field (name "MANUFACTURER PART NUMBER") "GRM155R71C104KA88D") (field (name "TOLERANCE") "10%"))
      (libsource (lib "Altium Content Vault") (part "236180d848d6139a670b325ea6854c9"))
    )
    (comp (ref "C1026")
      (value "0.1uF")
      (footprint "FP-GRM15-MFG")
      (description "CAP CER 0.1UF 16V X7R 0402")
      (fields (field (name "MANUFACTURER PART NUMBER") "GRM155R71C104KA88D") (field (name "TOLERANCE") "10%"))
      (libsource (lib "Altium Content Vault") (part "236180d848d6139a670b325ea6854c9"))
    )
    (comp (ref "C1027")
      (value "0.1uF")
      (footprint "FP-GRM15-MFG")
      (description "CAP CER 0.1UF 16V X7R 0402")
      (fields (field (name "MANUFACTURER PART NUMBER") "GRM155R71C104KA88D") (field (name "TOLERANCE") "10%"))
      (libsource (lib "Altium Content Vault") (part "236180d848d6139a670b325ea6854c9"))
    )
    (comp (ref "C1028")
      (value "0.1uF")
      (footprint "FP-GRM15-MFG")
      (description "CAP CER 0.1UF 16V X7R 0402")
      (fields (field (name "MANUFACTURER PART NUMBER") "GRM155R71C104KA88D") (field (name "TOLERANCE") "10%"))
      (libsource (lib "Altium Content Vault") (part "236180d848d6139a670b325ea6854c9"))
    )
    (comp (ref "C1029")
      (value "0.1uF")
      (footprint "FP-GRM15-MFG")
      (description "CAP CER 0.1UF 16V X7R 0402")
      (fields (field (name "MANUFACTURER PART NUMBER") "GRM155R71C104KA88D") (field (name "TOLERANCE") "10%"))
      (libsource (lib "Altium Content Vault") (part "236180d848d6139a670b325ea6854c9"))
    )
    (comp (ref "C1030")
      (value "0.1uF")
      (footprint "FP-GRM15-MFG")
      (description "CAP CER 0.1UF 16V X7R 0402")
      (fields (field (name "MANUFACTURER PART NUMBER") "GRM155R71C104KA88D") (field (name "TOLERANCE") "10%"))
      (libsource (lib "Altium Content Vault") (part "236180d848d6139a670b325ea6854c9"))
    )
    (comp (ref "C1031")
      (value "0.1uF")
      (footprint "FP-GRM15-MFG")
      (description "CAP CER 0.1UF 16V X7R 0402")
      (fields (field (name "MANUFACTURER PART NUMBER") "GRM155R71C104KA88D") (field (name "TOLERANCE") "10%"))
      (libsource (lib "Altium Content Vault") (part "236180d848d6139a670b325ea6854c9"))
    )
    (comp (ref "C1032")
      (value "10uF")
      (footprint "FP-C0805C-DG-MFG")
      (description "CAP CER 10UF 10V X5R 0805")
      (fields (field (name "TOLERANCE") "10%") (field (name "MANUFACTURER PART NUMBER") "C0805C106K8PACTU"))
      (libsource (lib "Altium Content Vault") (part "11868f565c42a9108669ba33697ecf6"))
    )
    (comp (ref "C1033")
      (value "0.1uF")
      (footprint "FP-GRM15-MFG")
      (description "CAP CER 0.1UF 16V X7R 0402")
      (fields (field (name "MANUFACTURER PART NUMBER") "GRM155R71C104KA88D") (field (name "TOLERANCE") "10%"))
      (libsource (lib "Altium Content Vault") (part "236180d848d6139a670b325ea6854c9"))
    )
    (comp (ref "C1034")
      (value "22uF")
      (footprint "FP-GRM21B-0_15-MFG")
      (description "Chip Multilayer Ceramic Capacitors for General Purpose, 0805, 22uF, X5R, 15%, 20%, 6.3V")
      (fields (field (name "VOLTAGE") "6.3V") (field (name "TOLERANCE") "20%"))
      (libsource (lib "Altium Content Vault") (part "b4654b650e69147ec39a6b967a45e02"))
    )
    (comp (ref "C1035")
      (value "1500pF")
      (footprint "FP-C0402-BB-MFG")
      (description "CAP CER 1500PF 50V X7R 0402")
      (fields
        (field (name "OCTOPART") "https://octopart.com/c0402c152k5ractu-kemet-125298")
        (field (name "TOLERANCE") "0.1")
      )
      (libsource (lib "Altium Content Vault") (part "b4654b650e69147ec39a6b967a45e02"))
    )
    (comp (ref "C1036")
      (value "0.1uF")
      (footprint "FP-GRM15-MFG")
      (description "CAP CER 0.1UF 16V X7R 0402")
      (fields (field (name "MANUFACTURER PART NUMBER") "GRM155R71C104KA88D") (field (name "TOLERANCE") "10%"))
      (libsource (lib "Altium Content Vault") (part "236180d848d6139a670b325ea6854c9"))
    )
    (comp (ref "C1037")
      (value "0.1uF")
      (footprint "FP-GRM15-MFG")
      (description "CAP CER 0.1UF 16V X7R 0402")
      (fields (field (name "MANUFACTURER PART NUMBER") "GRM155R71C104KA88D") (field (name "TOLERANCE") "10%"))
      (libsource (lib "Altium Content Vault") (part "236180d848d6139a670b325ea6854c9"))
    )
    (comp (ref "C1038")
      (value "0.1uF")
      (footprint "FP-GRM15-MFG")
      (description "CAP CER 0.1UF 16V X7R 0402")
      (fields (field (name "MANUFACTURER PART NUMBER") "GRM155R71C104KA88D") (field (name "TOLERANCE") "10%"))
      (libsource (lib "Altium Content Vault") (part "236180d848d6139a670b325ea6854c9"))
    )
    (comp (ref "C1039")
      (value "0.1uF")
      (footprint "FP-GRM15-MFG")
      (description "CAP CER 0.1UF 16V X7R 0402")
      (fields (field (name "MANUFACTURER PART NUMBER") "GRM155R71C104KA88D") (field (name "TOLERANCE") "10%"))
      (libsource (lib "Altium Content Vault") (part "236180d848d6139a670b325ea6854c9"))
    )
    (comp (ref "C1040")
      (value "22uF")
      (footprint "FP-GRM21B-0_15-MFG")
      (description "Chip Multilayer Ceramic Capacitors for General Purpose, 0805, 22uF, X5R, 15%, 20%, 6.3V")
      (fields (field (name "VOLTAGE") "6.3V") (field (name "TOLERANCE") "20%"))
      (libsource (lib "Altium Content Vault") (part "b4654b650e69147ec39a6b967a45e02"))
    )
    (comp (ref "C1041")
      (value "0.1uF")
      (footprint "FP-GRM15-MFG")
      (description "CAP CER 0.1UF 16V X7R 0402")
      (fields (field (name "MANUFACTURER PART NUMBER") "GRM155R71C104KA88D") (field (name "TOLERANCE") "10%"))
      (libsource (lib "Altium Content Vault") (part "236180d848d6139a670b325ea6854c9"))
    )
    (comp (ref "C1042")
      (value "2.2uF")
      (footprint "CAPC1005X55X30NL05T10")
      (fields (field (name "MANUFACTURER") "Kemet") (field (name "PART NUMBER") "C0402C225M9PACTU"))
      (libsource (lib "Altium Content Vault") (part "CAP"))
    )
    (comp (ref "C1043")
      (value "2.2uF")
      (footprint "CAPC1005X55X30NL05T10")
      (fields (field (name "MANUFACTURER") "Kemet") (field (name "PART NUMBER") "C0402C225M9PACTU"))
      (libsource (lib "Altium Content Vault") (part "CAP"))
    )
    (comp (ref "C1044")
      (value "3000pF")
      (footprint "FP-GRM155-0_05-IPC_B")
      (description "Chip Multilayer Ceramic Capacitors for General Purpose, 0402, 3000pF, U2J, -750ppm/°C, 5%, 10V")
      (fields (field (name "TOLERANCE") "5%"))
      (libsource (lib "Altium Content Vault") (part "02cd4be3c70576c341d710602a673aa"))
    )
    (comp (ref "C1045")
      (value "1500pF")
      (footprint "FP-C0402-BB-MFG")
      (description "CAP CER 1500PF 50V X7R 0402")
      (fields
        (field (name "OCTOPART") "https://octopart.com/c0402c152k5ractu-kemet-125298")
        (field (name "TOLERANCE") "0.1")
      )
      (libsource (lib "Altium Content Vault") (part "b4654b650e69147ec39a6b967a45e02"))
    )
    (comp (ref "C1046")
      (value "0.1uF")
      (footprint "FP-GRM15-MFG")
      (description "CAP CER 0.1UF 16V X7R 0402")
      (fields (field (name "MANUFACTURER PART NUMBER") "GRM155R71C104KA88D") (field (name "TOLERANCE") "10%"))
      (libsource (lib "Altium Content Vault") (part "236180d848d6139a670b325ea6854c9"))
    )
    (comp (ref "C1047")
      (value "0.1uF")
      (footprint "FP-GRM15-MFG")
      (description "CAP CER 0.1UF 16V X7R 0402")
      (fields (field (name "MANUFACTURER PART NUMBER") "GRM155R71C104KA88D") (field (name "TOLERANCE") "10%"))
      (libsource (lib "Altium Content Vault") (part "236180d848d6139a670b325ea6854c9"))
    )
    (comp (ref "C1048")
      (value "0.1uF")
      (footprint "FP-GRM15-MFG")
      (description "CAP CER 0.1UF 16V X7R 0402")
      (fields (field (name "MANUFACTURER PART NUMBER") "GRM155R71C104KA88D") (field (name "TOLERANCE") "10%"))
      (libsource (lib "Altium Content Vault") (part "236180d848d6139a670b325ea6854c9"))
    )
    (comp (ref "C1049")
      (value "0.1uF")
      (footprint "FP-GRM15-MFG")
      (description "CAP CER 0.1UF 16V X7R 0402")
      (fields (field (name "MANUFACTURER PART NUMBER") "GRM155R71C104KA88D") (field (name "TOLERANCE") "10%"))
      (libsource (lib "Altium Content Vault") (part "236180d848d6139a670b325ea6854c9"))
    )
    (comp (ref "C1050")
      (value "0.1uF")
      (footprint "FP-GRM15-MFG")
      (description "CAP CER 0.1UF 16V X7R 0402")
      (fields (field (name "MANUFACTURER PART NUMBER") "GRM155R71C104KA88D") (field (name "TOLERANCE") "10%"))
      (libsource (lib "Altium Content Vault") (part "236180d848d6139a670b325ea6854c9"))
    )
    (comp (ref "C1051")
      (value "0.1uF")
      (footprint "FP-GRM15-MFG")
      (description "CAP CER 0.1UF 16V X7R 0402")
      (fields (field (name "MANUFACTURER PART NUMBER") "GRM155R71C104KA88D") (field (name "TOLERANCE") "10%"))
      (libsource (lib "Altium Content Vault") (part "236180d848d6139a670b325ea6854c9"))
    )
    (comp (ref "C1052")
      (value "0.1uF")
      (footprint "FP-GRM15-MFG")
      (description "CAP CER 0.1UF 16V X7R 0402")
      (fields (field (name "MANUFACTURER PART NUMBER") "GRM155R71C104KA88D") (field (name "TOLERANCE") "10%"))
      (libsource (lib "Altium Content Vault") (part "236180d848d6139a670b325ea6854c9"))
    )
    (comp (ref "C1053")
      (value "0.1uF")
      (footprint "FP-GRM15-MFG")
      (description "CAP CER 0.1UF 16V X7R 0402")
      (fields (field (name "MANUFACTURER PART NUMBER") "GRM155R71C104KA88D") (field (name "TOLERANCE") "10%"))
      (libsource (lib "Altium Content Vault") (part "236180d848d6139a670b325ea6854c9"))
    )
    (comp (ref "C1054")
      (value "3000pF")
      (footprint "FP-GRM155-0_05-IPC_B")
      (description "Chip Multilayer Ceramic Capacitors for General Purpose, 0402, 3000pF, U2J, -750ppm/°C, 5%, 10V")
      (fields (field (name "TOLERANCE") "5%"))
      (libsource (lib "Altium Content Vault") (part "02cd4be3c70576c341d710602a673aa"))
    )
    (comp (ref "C1055")
      (value "1500pF")
      (footprint "FP-C0402-BB-MFG")
      (description "CAP CER 1500PF 50V X7R 0402")
      (fields
        (field (name "OCTOPART") "https://octopart.com/c0402c152k5ractu-kemet-125298")
        (field (name "TOLERANCE") "0.1")
      )
      (libsource (lib "Altium Content Vault") (part "b4654b650e69147ec39a6b967a45e02"))
    )
    (comp (ref "C1056")
      (value "22uF")
      (footprint "FP-GRM21B-0_15-MFG")
      (description "Chip Multilayer Ceramic Capacitors for General Purpose, 0805, 22uF, X5R, 15%, 20%, 6.3V")
      (fields (field (name "VOLTAGE") "6.3V") (field (name "TOLERANCE") "20%"))
      (libsource (lib "Altium Content Vault") (part "b4654b650e69147ec39a6b967a45e02"))
    )
    (comp (ref "C1057")
      (value "22uF")
      (footprint "FP-GRM21B-0_15-MFG")
      (description "Chip Multilayer Ceramic Capacitors for General Purpose, 0805, 22uF, X5R, 15%, 20%, 6.3V")
      (fields (field (name "VOLTAGE") "6.3V") (field (name "TOLERANCE") "20%"))
      (libsource (lib "Altium Content Vault") (part "b4654b650e69147ec39a6b967a45e02"))
    )
    (comp (ref "C1058")
      (value "22uF")
      (footprint "FP-GRM21B-0_15-MFG")
      (description "Chip Multilayer Ceramic Capacitors for General Purpose, 0805, 22uF, X5R, 15%, 20%, 6.3V")
      (fields (field (name "VOLTAGE") "6.3V") (field (name "TOLERANCE") "20%"))
      (libsource (lib "Altium Content Vault") (part "b4654b650e69147ec39a6b967a45e02"))
    )
    (comp (ref "C1059")
      (value "2.2uF")
      (footprint "CAPC1005X55X30NL05T10")
      (fields (field (name "MANUFACTURER") "Kemet") (field (name "PART NUMBER") "C0402C225M9PACTU"))
      (libsource (lib "Altium Content Vault") (part "CAP"))
    )
    (comp (ref "C1060")
      (value "2.2uF")
      (footprint "CAPC1005X55X30NL05T10")
      (fields (field (name "MANUFACTURER") "Kemet") (field (name "PART NUMBER") "C0402C225M9PACTU"))
      (libsource (lib "Altium Content Vault") (part "CAP"))
    )
    (comp (ref "C1061")
      (value "1uF")
      (footprint "CAPC1005X60X30LL05T10")
      (fields (field (name "PART NUMBER") "C0402C105K8PAC7867") (field (name "MANUFACTURER") "Kemet"))
      (libsource (lib "Altium Content Vault") (part "CAP"))
    )
    (comp (ref "C1062")
      (value "10uF")
      (footprint "FP-C0805C-DG-MFG")
      (description "CAP CER 10UF 10V X5R 0805")
      (fields (field (name "TOLERANCE") "10%") (field (name "MANUFACTURER PART NUMBER") "C0805C106K8PACTU"))
      (libsource (lib "Altium Content Vault") (part "11868f565c42a9108669ba33697ecf6"))
    )
    (comp (ref "C1063")
      (value "3000pF")
      (footprint "FP-GRM155-0_05-IPC_B")
      (description "Chip Multilayer Ceramic Capacitors for General Purpose, 0402, 3000pF, U2J, -750ppm/°C, 5%, 10V")
      (fields (field (name "TOLERANCE") "5%"))
      (libsource (lib "Altium Content Vault") (part "02cd4be3c70576c341d710602a673aa"))
    )
    (comp (ref "C1064")
      (value "4.7uF")
      (footprint "FP-GRM188-0_2-IPC_C")
      (description "Chip Multilayer Ceramic Capacitors for General Purpose, 0603, 4.7uF, X5R, 15%, 10%, 35V")
      (fields (field (name "VOLTAGE") "35V") (field (name "TOLERANCE") "10%"))
      (libsource (lib "Altium Content Vault") (part "11868f565c42a9108669ba33697ecf6"))
    )
    (comp (ref "C1065")
      (value "0.47uF")
      (footprint "FP-GRM188-0_1-e0_2_0_5-IPC_B")
      (description "Chip Multilayer Ceramic Capacitors for General Purpose, 0603, 0.47uF, X7R, 15%, 10%, 16V")
      (fields (field (name "VOLTAGE") "16V") (field (name "TOLERANCE") "10%"))
      (libsource (lib "Altium Content Vault") (part "11868f565c42a9108669ba33697ecf6"))
    )
    (comp (ref "C1066")
      (value "1uF")
      (footprint "CAPC1005X60X30LL05T10")
      (fields (field (name "PART NUMBER") "C0402C105K8PAC7867") (field (name "MANUFACTURER") "Kemet"))
      (libsource (lib "Altium Content Vault") (part "CAP"))
    )
    (comp (ref "C1067")
      (value "10uF")
      (footprint "FP-C0805C-DG-MFG")
      (description "CAP CER 10UF 10V X5R 0805")
      (fields (field (name "TOLERANCE") "10%") (field (name "MANUFACTURER PART NUMBER") "C0805C106K8PACTU"))
      (libsource (lib "Altium Content Vault") (part "11868f565c42a9108669ba33697ecf6"))
    )
    (comp (ref "C1068")
      (value "3000pF")
      (footprint "FP-GRM155-0_05-IPC_B")
      (description "Chip Multilayer Ceramic Capacitors for General Purpose, 0402, 3000pF, U2J, -750ppm/°C, 5%, 10V")
      (fields (field (name "TOLERANCE") "5%"))
      (libsource (lib "Altium Content Vault") (part "02cd4be3c70576c341d710602a673aa"))
    )
    (comp (ref "C1069")
      (value "4.7uF")
      (footprint "FP-GRM188-0_2-IPC_C")
      (description "Chip Multilayer Ceramic Capacitors for General Purpose, 0603, 4.7uF, X5R, 15%, 10%, 35V")
      (fields (field (name "VOLTAGE") "35V") (field (name "TOLERANCE") "10%"))
      (libsource (lib "Altium Content Vault") (part "11868f565c42a9108669ba33697ecf6"))
    )
    (comp (ref "C1070")
      (value "0.47uF")
      (footprint "FP-GRM188-0_1-e0_2_0_5-IPC_B")
      (description "Chip Multilayer Ceramic Capacitors for General Purpose, 0603, 0.47uF, X7R, 15%, 10%, 16V")
      (fields (field (name "VOLTAGE") "16V") (field (name "TOLERANCE") "10%"))
      (libsource (lib "Altium Content Vault") (part "11868f565c42a9108669ba33697ecf6"))
    )
    (comp (ref "C1071")
      (value "1uF")
      (footprint "CAPC1005X60X30LL05T10")
      (fields (field (name "PART NUMBER") "C0402C105K8PAC7867") (field (name "MANUFACTURER") "Kemet"))
      (libsource (lib "Altium Content Vault") (part "CAP"))
    )
    (comp (ref "C1072")
      (value "10uF")
      (footprint "FP-C0805C-DG-MFG")
      (description "CAP CER 10UF 10V X5R 0805")
      (fields (field (name "TOLERANCE") "10%") (field (name "MANUFACTURER PART NUMBER") "C0805C106K8PACTU"))
      (libsource (lib "Altium Content Vault") (part "11868f565c42a9108669ba33697ecf6"))
    )
    (comp (ref "C1073")
      (value "1uF")
      (footprint "CAPC1005X60X30LL05T10")
      (fields (field (name "PART NUMBER") "C0402C105K8PAC7867") (field (name "MANUFACTURER") "Kemet"))
      (libsource (lib "Altium Content Vault") (part "CAP"))
    )
    (comp (ref "C1074")
      (value "10uF")
      (footprint "FP-C0805C-DG-MFG")
      (description "CAP CER 10UF 10V X5R 0805")
      (fields (field (name "TOLERANCE") "10%") (field (name "MANUFACTURER PART NUMBER") "C0805C106K8PACTU"))
      (libsource (lib "Altium Content Vault") (part "11868f565c42a9108669ba33697ecf6"))
    )
    (comp (ref "IC61")
      (value "LS1043ASN8QQB")
      (footprint "SamacSys:BGA780C80P28X28_2300X2300X261")
      (description "Integrated Circuit")
      (fields (field (name "MOUSER PART NUMBER") "771-LS1043ASN8QQB"))
      (libsource (lib "SamacSys") (part "LS1043ASN8QQB"))
    )
    (comp (ref "L45")
      (value "220nH")
      (footprint "FP-MPLCG0530-MFG")
      (description "FIXED IND 220NH 14.1A 3.7 MOHM")
      (fields
        (field (name "OCTOPART") "https://octopart.com/mplcg0530lr22-kemet-30531716")
        (field (name "MANUFACTURER") "KEMET")
      )
      (libsource (lib "Altium Content Vault") (part "725321dda6339637d4d059423bc1c3c"))
    )
    (comp (ref "L46")
      (value "220nH")
      (footprint "FP-MPLCG0530-MFG")
      (description "FIXED IND 220NH 14.1A 3.7 MOHM")
      (fields
        (field (name "OCTOPART") "https://octopart.com/mplcg0530lr22-kemet-30531716")
        (field (name "MANUFACTURER") "KEMET")
      )
      (libsource (lib "Altium Content Vault") (part "725321dda6339637d4d059423bc1c3c"))
    )
    (comp (ref "L47")
      (value "220nH")
      (footprint "FP-MPLCG0530-MFG")
      (description "FIXED IND 220NH 14.1A 3.7 MOHM")
      (fields
        (field (name "OCTOPART") "https://octopart.com/mplcg0530lr22-kemet-30531716")
        (field (name "MANUFACTURER") "KEMET")
      )
      (libsource (lib "Altium Content Vault") (part "725321dda6339637d4d059423bc1c3c"))
    )
    (comp (ref "L48")
      (value "220nH")
      (footprint "FP-MPLCG0530-MFG")
      (description "FIXED IND 220NH 14.1A 3.7 MOHM")
      (fields
        (field (name "OCTOPART") "https://octopart.com/mplcg0530lr22-kemet-30531716")
        (field (name "MANUFACTURER") "KEMET")
      )
      (libsource (lib "Altium Content Vault") (part "725321dda6339637d4d059423bc1c3c"))
    )
    (comp (ref "L49")
      (value "220nH")
      (footprint "FP-MPLCG0530-MFG")
      (description "FIXED IND 220NH 14.1A 3.7 MOHM")
      (fields
        (field (name "OCTOPART") "https://octopart.com/mplcg0530lr22-kemet-30531716")
        (field (name "MANUFACTURER") "KEMET")
      )
      (libsource (lib "Altium Content Vault") (part "725321dda6339637d4d059423bc1c3c"))
    )
    (comp (ref "L50")
      (value "220nH")
      (footprint "FP-MPLCG0530-MFG")
      (description "FIXED IND 220NH 14.1A 3.7 MOHM")
      (fields
        (field (name "OCTOPART") "https://octopart.com/mplcg0530lr22-kemet-30531716")
        (field (name "MANUFACTURER") "KEMET")
      )
      (libsource (lib "Altium Content Vault") (part "725321dda6339637d4d059423bc1c3c"))
    )
    (comp (ref "L51")
      (value "220nH")
      (footprint "FP-MPLCG0530-MFG")
      (description "FIXED IND 220NH 14.1A 3.7 MOHM")
      (fields
        (field (name "OCTOPART") "https://octopart.com/mplcg0530lr22-kemet-30531716")
        (field (name "MANUFACTURER") "KEMET")
      )
      (libsource (lib "Altium Content Vault") (part "725321dda6339637d4d059423bc1c3c"))
    )
    (comp (ref "L52")
      (value "220nH")
      (footprint "FP-MPLCG0530-MFG")
      (description "FIXED IND 220NH 14.1A 3.7 MOHM")
      (fields
        (field (name "OCTOPART") "https://octopart.com/mplcg0530lr22-kemet-30531716")
        (field (name "MANUFACTURER") "KEMET")
      )
      (libsource (lib "Altium Content Vault") (part "725321dda6339637d4d059423bc1c3c"))
    )
    (comp (ref "L53")
      (value "220nH")
      (footprint "FP-MPLCG0530-MFG")
      (description "FIXED IND 220NH 14.1A 3.7 MOHM")
      (fields
        (field (name "OCTOPART") "https://octopart.com/mplcg0530lr22-kemet-30531716")
        (field (name "MANUFACTURER") "KEMET")
      )
      (libsource (lib "Altium Content Vault") (part "725321dda6339637d4d059423bc1c3c"))
    )
    (comp (ref "L54")
      (value "220nH")
      (footprint "FP-MPLCG0530-MFG")
      (description "FIXED IND 220NH 14.1A 3.7 MOHM")
      (fields
        (field (name "OCTOPART") "https://octopart.com/mplcg0530lr22-kemet-30531716")
        (field (name "MANUFACTURER") "KEMET")
      )
      (libsource (lib "Altium Content Vault") (part "725321dda6339637d4d059423bc1c3c"))
    )
    (comp (ref "L55")
      (value "220nH")
      (footprint "FP-MPLCG0530-MFG")
      (description "FIXED IND 220NH 14.1A 3.7 MOHM")
      (fields
        (field (name "OCTOPART") "https://octopart.com/mplcg0530lr22-kemet-30531716")
        (field (name "MANUFACTURER") "KEMET")
      )
      (libsource (lib "Altium Content Vault") (part "725321dda6339637d4d059423bc1c3c"))
    )
    (comp (ref "L56")
      (value "220nH")
      (footprint "FP-MPLCG0530-MFG")
      (description "FIXED IND 220NH 14.1A 3.7 MOHM")
      (fields
        (field (name "OCTOPART") "https://octopart.com/mplcg0530lr22-kemet-30531716")
        (field (name "MANUFACTURER") "KEMET")
      )
      (libsource (lib "Altium Content Vault") (part "725321dda6339637d4d059423bc1c3c"))
    )
    (comp (ref "L57")
      (value "220nH")
      (footprint "FP-MPLCG0530-MFG")
      (description "FIXED IND 220NH 14.1A 3.7 MOHM")
      (fields
        (field (name "OCTOPART") "https://octopart.com/mplcg0530lr22-kemet-30531716")
        (field (name "MANUFACTURER") "KEMET")
      )
      (libsource (lib "Altium Content Vault") (part "725321dda6339637d4d059423bc1c3c"))
    )
    (comp (ref "P12")
      (value "5-146280-2")
      (footprint "TECO-5-146280-2_V")
      (fields (field (name "MANUFACTURER") "TE Connectivity"))
      (libsource (lib "") (part "CN-1P-M-R2_1"))
    )
    (comp (ref "P13")
      (value "5-146280-2")
      (footprint "TECO-5-146280-2_V")
      (fields (field (name "MANUFACTURER") "TE Connectivity"))
      (libsource (lib "Altium Content Vault") (part "CN-1P-M-R2"))
    )
    (comp (ref "P14")
      (value "5-146280-2")
      (footprint "TECO-5-146280-2_V")
      (fields (field (name "MANUFACTURER") "TE Connectivity"))
      (libsource (lib "Altium Content Vault") (part "CN-1P-M-R2"))
    )
    (comp (ref "P15")
      (value "5-146280-2")
      (footprint "TECO-5-146280-2_V")
      (fields (field (name "MANUFACTURER") "TE Connectivity"))
      (libsource (lib "Altium Content Vault") (part "CN-1P-M-R2"))
    )
    (comp (ref "R536")
      (value "10")
      (footprint "RESC1005X40X25NL05T05")
      (fields (field (name "PART NUMBER") "CRCW040210R0FKED") (field (name "MANUFACTURER") "Vishay Dale"))
      (libsource (lib "Altium Content Vault") (part "RES"))
    )
    (comp (ref "R537")
      (value "10")
      (footprint "RESC1005X40X25NL05T05")
      (fields (field (name "PART NUMBER") "CRCW040210R0FKED") (field (name "MANUFACTURER") "Vishay Dale"))
      (libsource (lib "Altium Content Vault") (part "RES"))
    )
    (comp (ref "R538")
      (value "330")
      (footprint "FP-CRCW0402-e3-MFG")
      (description "RES Thick Film, 330Ω, 1%, 0.063W, 100ppm/°C, 0402")
      (fields (field (name "TOLERANCE") "1%"))
      (libsource (lib "Altium Content Vault") (part "1029c3af85768c4190bb7ad29bc67b5"))
    )
    (comp (ref "R539")
      (value "330")
      (footprint "FP-CRCW0402-e3-MFG")
      (description "RES Thick Film, 330Ω, 1%, 0.063W, 100ppm/°C, 0402")
      (fields (field (name "TOLERANCE") "1%"))
      (libsource (lib "Altium Content Vault") (part "1029c3af85768c4190bb7ad29bc67b5"))
    )
    (comp (ref "R540")
      (value "330")
      (footprint "FP-CRCW0402-e3-MFG")
      (description "RES Thick Film, 330Ω, 1%, 0.063W, 100ppm/°C, 0402")
      (fields (field (name "TOLERANCE") "1%"))
      (libsource (lib "Altium Content Vault") (part "1029c3af85768c4190bb7ad29bc67b5"))
    )
    (comp (ref "R541")
      (value "330")
      (footprint "FP-CRCW0402-e3-MFG")
      (description "RES Thick Film, 330Ω, 1%, 0.063W, 100ppm/°C, 0402")
      (fields (field (name "TOLERANCE") "1%"))
      (libsource (lib "Altium Content Vault") (part "1029c3af85768c4190bb7ad29bc67b5"))
    )
    (comp (ref "R542")
      (value "330")
      (footprint "FP-CRCW0402-e3-MFG")
      (description "RES Thick Film, 330Ω, 1%, 0.063W, 100ppm/°C, 0402")
      (fields (field (name "TOLERANCE") "1%"))
      (libsource (lib "Altium Content Vault") (part "1029c3af85768c4190bb7ad29bc67b5"))
    )
    (comp (ref "R543")
      (value "5.1")
      (footprint "RESC1005X40X25LL05T05")
      (fields (field (name "PART NUMBER") "CRCW04025R10FKED") (field (name "MANUFACTURER") "Vishay Dale"))
      (libsource (lib "Altium Content Vault") (part "RES"))
    )
    (comp (ref "R544")
      (value "5.1")
      (footprint "RESC1005X40X25LL05T05")
      (fields (field (name "PART NUMBER") "CRCW04025R10FKED") (field (name "MANUFACTURER") "Vishay Dale"))
      (libsource (lib "Altium Content Vault") (part "RES"))
    )
    (comp (ref "R545")
      (value "0.33")
      (footprint "RESC2013X50X40LL20T20")
      (fields (field (name "MANUFACTURER") "Susumu") (field (name "PART NUMBER") "RP2012T-R33-F"))
      (libsource (lib "Altium Content Vault") (part "RES"))
    )
    (comp (ref "R546")
      (value "0.33")
      (footprint "RESC2013X50X40LL20T20")
      (fields (field (name "MANUFACTURER") "Susumu") (field (name "PART NUMBER") "RP2012T-R33-F"))
      (libsource (lib "Altium Content Vault") (part "RES"))
    )
    (comp (ref "R547")
      (value "5.1")
      (footprint "RESC1005X40X25LL05T05")
      (fields (field (name "PART NUMBER") "CRCW04025R10FKED") (field (name "MANUFACTURER") "Vishay Dale"))
      (libsource (lib "Altium Content Vault") (part "RES"))
    )
    (comp (ref "R548")
      (value "5.1")
      (footprint "RESC1005X40X25LL05T05")
      (fields (field (name "PART NUMBER") "CRCW04025R10FKED") (field (name "MANUFACTURER") "Vishay Dale"))
      (libsource (lib "Altium Content Vault") (part "RES"))
    )
  )
  (nets
    (net (code "1") (name "+1V8") (class "Default")
      (node (ref "C1031") (pin "2") (pinfunction "2_2") (pintype "passive"))
      (node (ref "C1032") (pin "1") (pinfunction "1_1") (pintype "passive"))
      (node (ref "C1039") (pin "2") (pinfunction "2_2") (pintype "passive"))
      (node (ref "C1040") (pin "1") (pinfunction "1_1") (pintype "passive"))
      (node (ref "C983") (pin "2") (pinfunction "2_2") (pintype "passive"))
      (node (ref "C984") (pin "2") (pinfunction "2_2") (pintype "passive"))
      (node (ref "C985") (pin "2") (pinfunction "2_2") (pintype "passive"))
      (node (ref "C986") (pin "2") (pinfunction "2_2") (pintype "passive"))
      (node (ref "C987") (pin "2") (pinfunction "2_2") (pintype "passive"))
      (node (ref "C988") (pin "2") (pinfunction "2_2") (pintype "passive"))
      (node (ref "C989") (pin "2") (pinfunction "2_2") (pintype "passive"))
      (node (ref "C990") (pin "1") (pinfunction "1_1") (pintype "passive"))
      (node (ref "C991") (pin "1") (pinfunction "1_1") (pintype "passive"))
      (node (ref "IC61") (pin "J12") (pinfunction "OVDD1_J12") (pintype "passive"))
      (node (ref "IC61") (pin "J13") (pinfunction "OVDD2_J13") (pintype "passive"))
      (node (ref "IC61") (pin "J14") (pinfunction "OVDD3_J14") (pintype "passive"))
      (node (ref "IC61") (pin "J15") (pinfunction "OVDD4_J15") (pintype "passive"))
      (node (ref "IC61") (pin "J16") (pinfunction "OVDD5_J16") (pintype "passive"))
      (node (ref "IC61") (pin "J17") (pinfunction "OVDD6_J17") (pintype "passive"))
      (node (ref "IC61") (pin "N7") (pinfunction "OVDD7_N7") (pintype "passive"))
      (node (ref "IC61") (pin "T6") (pinfunction "TH_VDD_T6") (pintype "passive"))
      (node (ref "L49") (pin "2") (pinfunction "2_2") (pintype "passive"))
      (node (ref "P13") (pin "1") (pinfunction "1_1") (pintype "passive"))
      (node (ref "P14") (pin "2") (pinfunction "2_2") (pintype "passive"))
      (node (ref "R539") (pin "2") (pinfunction "2_2") (pintype "passive"))
      (node (ref "R543") (pin "1") (pinfunction "1_1") (pintype "passive"))
      (node (ref "R544") (pin "1") (pinfunction "1_1") (pintype "passive"))
      (node (ref "R547") (pin "1") (pinfunction "1_1") (pintype "passive"))
      (node (ref "R548") (pin "1") (pinfunction "1_1") (pintype "passive"))
    )
    (net (code "2") (name "+2V5") (class "Default")
      (node (ref "L48") (pin "2") (pinfunction "2_2") (pintype "passive"))
      (node (ref "L51") (pin "1") (pinfunction "1_1") (pintype "passive"))
    )
    (net (code "3") (name "+3V3") (class "Default")
      (node (ref "C1013") (pin "2") (pinfunction "2_2") (pintype "passive"))
      (node (ref "C1014") (pin "2") (pinfunction "2_2") (pintype "passive"))
      (node (ref "C1015") (pin "1") (pinfunction "1_1") (pintype "passive"))
      (node (ref "IC61") (pin "K8") (pinfunction "DVDD1_K8") (pintype "passive"))
      (node (ref "IC61") (pin "L8") (pinfunction "DVDD2_L8") (pintype "passive"))
      (node (ref "L47") (pin "2") (pinfunction "2_2") (pintype "passive"))
      (node (ref "L50") (pin "2") (pinfunction "2_2") (pintype "passive"))
    )
    (net (code "4") (name "+CPU_VDD") (class "Default")
      (node (ref "C923") (pin "1") (pinfunction "1_1") (pintype "passive"))
      (node (ref "C924") (pin "1") (pinfunction "1_1") (pintype "passive"))
      (node (ref "C925") (pin "1") (pinfunction "1_1") (pintype "passive"))
      (node (ref "C926") (pin "1") (pinfunction "1_1") (pintype "passive"))
      (node (ref "C927") (pin "1") (pinfunction "1_1") (pintype "passive"))
      (node (ref "C928") (pin "1") (pinfunction "1_1") (pintype "passive"))
      (node (ref "C929") (pin "1") (pinfunction "1_1") (pintype "passive"))
      (node (ref "C930") (pin "1") (pinfunction "1_1") (pintype "passive"))
      (node (ref "C931") (pin "1") (pinfunction "1_1") (pintype "passive"))
      (node (ref "C932") (pin "2") (pinfunction "2_2") (pintype "passive"))
      (node (ref "C933") (pin "2") (pinfunction "2_2") (pintype "passive"))
      (node (ref "C934") (pin "2") (pinfunction "2_2") (pintype "passive"))
      (node (ref "C935") (pin "2") (pinfunction "2_2") (pintype "passive"))
      (node (ref "C936") (pin "2") (pinfunction "2_2") (pintype "passive"))
      (node (ref "C937") (pin "2") (pinfunction "2_2") (pintype "passive"))
      (node (ref "C938") (pin "2") (pinfunction "2_2") (pintype "passive"))
      (node (ref "C939") (pin "2") (pinfunction "2_2") (pintype "passive"))
      (node (ref "C940") (pin "2") (pinfunction "2_2") (pintype "passive"))
      (node (ref "C941") (pin "2") (pinfunction "2_2") (pintype "passive"))
      (node (ref "C942") (pin "1") (pinfunction "1_1") (pintype "passive"))
      (node (ref "C943") (pin "1") (pinfunction "1_1") (pintype "passive"))
      (node (ref "C944") (pin "1") (pinfunction "1_1") (pintype "passive"))
      (node (ref "C949") (pin "2") (pinfunction "2_2") (pintype "passive"))
      (node (ref "C950") (pin "2") (pinfunction "2_2") (pintype "passive"))
      (node (ref "C951") (pin "2") (pinfunction "2_2") (pintype "passive"))
      (node (ref "C952") (pin "2") (pinfunction "2_2") (pintype "passive"))
      (node (ref "C953") (pin "2") (pinfunction "2_2") (pintype "passive"))
      (node (ref "C954") (pin "2") (pinfunction "2_2") (pintype "passive"))
      (node (ref "C955") (pin "2") (pinfunction "2_2") (pintype "passive"))
      (node (ref "C956") (pin "2") (pinfunction "2_2") (pintype "passive"))
      (node (ref "C957") (pin "2") (pinfunction "2_2") (pintype "passive"))
      (node (ref "C958") (pin "2") (pinfunction "2_2") (pintype "passive"))
      (node (ref "C959") (pin "1") (pinfunction "1_1") (pintype "passive"))
      (node (ref "C960") (pin "1") (pinfunction "1_1") (pintype "passive"))
      (node (ref "C961") (pin "1") (pinfunction "1_1") (pintype "passive"))
      (node (ref "C966") (pin "2") (pinfunction "2_2") (pintype "passive"))
      (node (ref "C967") (pin "2") (pinfunction "2_2") (pintype "passive"))
      (node (ref "C968") (pin "2") (pinfunction "2_2") (pintype "passive"))
      (node (ref "C969") (pin "2") (pinfunction "2_2") (pintype "passive"))
      (node (ref "C970") (pin "2") (pinfunction "2_2") (pintype "passive"))
      (node (ref "C971") (pin "2") (pinfunction "2_2") (pintype "passive"))
      (node (ref "C972") (pin "2") (pinfunction "2_2") (pintype "passive"))
      (node (ref "C973") (pin "2") (pinfunction "2_2") (pintype "passive"))
      (node (ref "C974") (pin "2") (pinfunction "2_2") (pintype "passive"))
      (node (ref "C975") (pin "2") (pinfunction "2_2") (pintype "passive"))
      (node (ref "C976") (pin "1") (pinfunction "1_1") (pintype "passive"))
      (node (ref "C977") (pin "1") (pinfunction "1_1") (pintype "passive"))
      (node (ref "C978") (pin "1") (pinfunction "1_1") (pintype "passive"))
      (node (ref "IC61") (pin "K13") (pinfunction "VDD01_K13") (pintype "passive"))
      (node (ref "IC61") (pin "K15") (pinfunction "VDD02_K15") (pintype "passive"))
      (node (ref "IC61") (pin "K17") (pinfunction "VDD03_K17") (pintype "passive"))
      (node (ref "IC61") (pin "L10") (pinfunction "VDD04_L10") (pintype "passive"))
      (node (ref "IC61") (pin "L12") (pinfunction "VDD05_L12") (pintype "passive"))
      (node (ref "IC61") (pin "L14") (pinfunction "VDD06_L14") (pintype "passive"))
      (node (ref "IC61") (pin "L16") (pinfunction "VDD07_L16") (pintype "passive"))
      (node (ref "IC61") (pin "M11") (pinfunction "VDD09_M11") (pintype "passive"))
      (node (ref "IC61") (pin "M13") (pinfunction "VDD10_M13") (pintype "passive"))
      (node (ref "IC61") (pin "M15") (pinfunction "VDD11_M15") (pintype "passive"))
      (node (ref "IC61") (pin "M17") (pinfunction "VDD12_M17") (pintype "passive"))
      (node (ref "IC61") (pin "M9") (pinfunction "VDD08_M9") (pintype "passive"))
      (node (ref "IC61") (pin "N10") (pinfunction "VDD14_N10") (pintype "passive"))
      (node (ref "IC61") (pin "N12") (pinfunction "VDD15_N12") (pintype "passive"))
      (node (ref "IC61") (pin "N14") (pinfunction "VDD16_N14") (pintype "passive"))
      (node (ref "IC61") (pin "N16") (pinfunction "VDD17_N16") (pintype "passive"))
      (node (ref "IC61") (pin "N8") (pinfunction "VDD13_N8") (pintype "passive"))
      (node (ref "IC61") (pin "P11") (pinfunction "VDD19_P11") (pintype "passive"))
      (node (ref "IC61") (pin "P13") (pinfunction "VDD20_P13") (pintype "passive"))
      (node (ref "IC61") (pin "P15") (pinfunction "VDD21_P15") (pintype "passive"))
      (node (ref "IC61") (pin "P17") (pinfunction "VDD22_P17") (pintype "passive"))
      (node (ref "IC61") (pin "P9") (pinfunction "VDD18_P9") (pintype "passive"))
      (node (ref "IC61") (pin "R10") (pinfunction "VDD24_R10") (pintype "passive"))
      (node (ref "IC61") (pin "R12") (pinfunction "VDD25_R12") (pintype "passive"))
      (node (ref "IC61") (pin "R14") (pinfunction "VDD26_R14") (pintype "passive"))
      (node (ref "IC61") (pin "R16") (pinfunction "VDD27_R16") (pintype "passive"))
      (node (ref "IC61") (pin "R18") (pinfunction "VDD28_R18") (pintype "passive"))
      (node (ref "IC61") (pin "R8") (pinfunction "VDD23_R8") (pintype "passive"))
      (node (ref "IC61") (pin "T11") (pinfunction "VDD30_T11") (pintype "passive"))
      (node (ref "IC61") (pin "T13") (pinfunction "VDD31_T13") (pintype "passive"))
      (node (ref "IC61") (pin "T9") (pinfunction "VDD29_T9") (pintype "passive"))
      (node (ref "IC61") (pin "U10") (pinfunction "VDD33_U10") (pintype "passive"))
      (node (ref "IC61") (pin "U8") (pinfunction "VDD32_U8") (pintype "passive"))
      (node (ref "L45") (pin "2") (pinfunction "2_2") (pintype "passive"))
      (node (ref "L46") (pin "2") (pinfunction "2_2") (pintype "passive"))
      (node (ref "L52") (pin "1") (pinfunction "1_1") (pintype "passive"))
      (node (ref "L54") (pin "1") (pinfunction "1_1") (pintype "passive"))
      (node (ref "P12") (pin "2") (pinfunction "2_2") (pintype "passive"))
      (node (ref "P15") (pin "2") (pinfunction "2_2") (pintype "passive"))
    )
    (net (code "5") (name "+GVDD") (class "Default")
      (node (ref "IC61") (pin "AA20") (pinfunction "G1VDD18_AA20") (pintype "passive"))
      (node (ref "IC61") (pin "AB22") (pinfunction "G1VDD19_AB22") (pintype "passive"))
      (node (ref "IC61") (pin "AB24") (pinfunction "G1VDD20_AB24") (pintype "passive"))
      (node (ref "IC61") (pin "AD22") (pinfunction "G1VDD21_AD22") (pintype "passive"))
      (node (ref "IC61") (pin "AD24") (pinfunction "G1VDD23_AD24") (pintype "passive"))
      (node (ref "IC61") (pin "AD25") (pinfunction "G1VDD22_AD25") (pintype "passive"))
      (node (ref "IC61") (pin "J18") (pinfunction "G1VDD01_J18") (pintype "passive"))
      (node (ref "IC61") (pin "K18") (pinfunction "G1VDD02_K18") (pintype "passive"))
      (node (ref "IC61") (pin "K20") (pinfunction "G1VDD03_K20") (pintype "passive"))
      (node (ref "IC61") (pin "L18") (pinfunction "G1VDD04_L18") (pintype "passive"))
      (node (ref "IC61") (pin "M18") (pinfunction "G1VDD05_M18") (pintype "passive"))
      (node (ref "IC61") (pin "M20") (pinfunction "G1VDD06_M20") (pintype "passive"))
      (node (ref "IC61") (pin "N18") (pinfunction "G1VDD07_N18") (pintype "passive"))
      (node (ref "IC61") (pin "P18") (pinfunction "G1VDD08_P18") (pintype "passive"))
      (node (ref "IC61") (pin "P20") (pinfunction "G1VDD09_P20") (pintype "passive"))
      (node (ref "IC61") (pin "R21") (pinfunction "G1VDD10_R21") (pintype "passive"))
      (node (ref "IC61") (pin "R23") (pinfunction "G1VDD11_R23") (pintype "passive"))
      (node (ref "IC61") (pin "T22") (pinfunction "G1VDD12_T22") (pintype "passive"))
      (node (ref "IC61") (pin "T24") (pinfunction "G1VDD13_T24") (pintype "passive"))
      (node (ref "IC61") (pin "V22") (pinfunction "G1VDD14_V22") (pintype "passive"))
      (node (ref "IC61") (pin "V24") (pinfunction "G1VDD15_V24") (pintype "passive"))
      (node (ref "IC61") (pin "Y22") (pinfunction "G1VDD16_Y22") (pintype "passive"))
      (node (ref "IC61") (pin "Y24") (pinfunction "G1VDD17_Y24") (pintype "passive"))
    )
    (net (code "6") (name "+GVVD") (class "Default")
      (node (ref "C1000") (pin "1") (pinfunction "1_1") (pintype "passive"))
      (node (ref "C1001") (pin "2") (pinfunction "2_2") (pintype "passive"))
      (node (ref "C1002") (pin "2") (pinfunction "2_2") (pintype "passive"))
      (node (ref "C1003") (pin "2") (pinfunction "2_2") (pintype "passive"))
      (node (ref "C1004") (pin "2") (pinfunction "2_2") (pintype "passive"))
      (node (ref "C1005") (pin "2") (pinfunction "2_2") (pintype "passive"))
      (node (ref "C1006") (pin "2") (pinfunction "2_2") (pintype "passive"))
      (node (ref "C1007") (pin "2") (pinfunction "2_2") (pintype "passive"))
      (node (ref "C1008") (pin "2") (pinfunction "2_2") (pintype "passive"))
      (node (ref "C1009") (pin "2") (pinfunction "2_2") (pintype "passive"))
      (node (ref "C1010") (pin "2") (pinfunction "2_2") (pintype "passive"))
      (node (ref "C1011") (pin "2") (pinfunction "2_2") (pintype "passive"))
      (node (ref "C1012") (pin "2") (pinfunction "2_2") (pintype "passive"))
      (node (ref "C1018") (pin "2") (pinfunction "2_2") (pintype "passive"))
      (node (ref "C1019") (pin "2") (pinfunction "2_2") (pintype "passive"))
      (node (ref "C1020") (pin "2") (pinfunction "2_2") (pintype "passive"))
      (node (ref "C1021") (pin "2") (pinfunction "2_2") (pintype "passive"))
      (node (ref "C1022") (pin "2") (pinfunction "2_2") (pintype "passive"))
      (node (ref "C1023") (pin "2") (pinfunction "2_2") (pintype "passive"))
      (node (ref "C1024") (pin "2") (pinfunction "2_2") (pintype "passive"))
      (node (ref "C1025") (pin "2") (pinfunction "2_2") (pintype "passive"))
      (node (ref "C1026") (pin "2") (pinfunction "2_2") (pintype "passive"))
      (node (ref "C1027") (pin "2") (pinfunction "2_2") (pintype "passive"))
      (node (ref "C1028") (pin "2") (pinfunction "2_2") (pintype "passive"))
      (node (ref "C992") (pin "1") (pinfunction "1_1") (pintype "passive"))
      (node (ref "C993") (pin "1") (pinfunction "1_1") (pintype "passive"))
      (node (ref "C994") (pin "1") (pinfunction "1_1") (pintype "passive"))
      (node (ref "C995") (pin "1") (pinfunction "1_1") (pintype "passive"))
      (node (ref "C996") (pin "1") (pinfunction "1_1") (pintype "passive"))
      (node (ref "C997") (pin "1") (pinfunction "1_1") (pintype "passive"))
      (node (ref "C998") (pin "1") (pinfunction "1_1") (pintype "passive"))
      (node (ref "C999") (pin "1") (pinfunction "1_1") (pintype "passive"))
    )
    (net (code "7") (name "/AVDD_CGA1") (class "Default")
      (node (ref "C1061") (pin "2") (pinfunction "2_2") (pintype "passive"))
      (node (ref "C1062") (pin "1") (pinfunction "1_1") (pintype "passive"))
      (node (ref "IC61") (pin "G12") (pinfunction "AVDD_CGA1_G12") (pintype "passive"))
      (node (ref "R543") (pin "2") (pinfunction "2_2") (pintype "passive"))
    )
    (net (code "8") (name "/AVDD_CGA2") (class "Default")
      (node (ref "C1066") (pin "2") (pinfunction "2_2") (pintype "passive"))
      (node (ref "C1067") (pin "1") (pinfunction "1_1") (pintype "passive"))
      (node (ref "IC61") (pin "G11") (pinfunction "AVDD_CGA2_G11") (pintype "passive"))
      (node (ref "R544") (pin "2") (pinfunction "2_2") (pintype "passive"))
    )
    (net (code "9") (name "/AVDD_DDR1") (class "Default")
      (node (ref "C1073") (pin "2") (pinfunction "2_2") (pintype "passive"))
      (node (ref "C1074") (pin "1") (pinfunction "1_1") (pintype "passive"))
      (node (ref "IC61") (pin "T19") (pinfunction "AVDD_D1_T19") (pintype "passive"))
      (node (ref "R548") (pin "2") (pinfunction "2_2") (pintype "passive"))
    )
    (net (code "10") (name "/AVDD_PLAT") (class "Default")
      (node (ref "C1071") (pin "2") (pinfunction "2_2") (pintype "passive"))
      (node (ref "C1072") (pin "1") (pinfunction "1_1") (pintype "passive"))
      (node (ref "IC61") (pin "G13") (pinfunction "AVDD_PLAT_G13") (pintype "passive"))
      (node (ref "R547") (pin "2") (pinfunction "2_2") (pintype "passive"))
    )
    (net (code "11") (name "/AVDD_SRDS1_PLL1") (class "Default")
      (node (ref "C1063") (pin "1") (pinfunction "1_1") (pintype "passive"))
      (node (ref "C1064") (pin "1") (pinfunction "1_1") (pintype "passive"))
      (node (ref "C1065") (pin "1") (pinfunction "1_1") (pintype "passive"))
      (node (ref "IC61") (pin "W12") (pinfunction "AVDD_SD1_PLL1_W12") (pintype "passive"))
      (node (ref "R545") (pin "2") (pinfunction "2_2") (pintype "passive"))
    )
    (net (code "12") (name "/AVDD_SRDS1_PLL2") (class "Default")
      (node (ref "C1068") (pin "1") (pinfunction "1_1") (pintype "passive"))
      (node (ref "C1069") (pin "1") (pinfunction "1_1") (pintype "passive"))
      (node (ref "C1070") (pin "1") (pinfunction "1_1") (pintype "passive"))
      (node (ref "IC61") (pin "V19") (pinfunction "AVDD_SD1_PLL2_V19") (pintype "passive"))
      (node (ref "R546") (pin "2") (pinfunction "2_2") (pintype "passive"))
    )
    (net (code "13") (name "/CPU_GND_SENSE") (class "Default")
      (node (ref "R537") (pin "2") (pinfunction "2_2") (pintype "passive"))
    )
    (net (code "14") (name "/CPU_VDD_SENSE") (class "Default")
      (node (ref "R536") (pin "2") (pinfunction "2_2") (pintype "passive"))
    )
    (net (code "15") (name "/PWR_PROG_MTR") (class "Default")
      (node (ref "C1029") (pin "2") (pinfunction "2_2") (pintype "passive"))
      (node (ref "IC61") (pin "G14") (pinfunction "PROG_MTR_G14") (pintype "passive"))
      (node (ref "P14") (pin "1") (pinfunction "1_1") (pintype "passive"))
      (node (ref "R540") (pin "2") (pinfunction "2_2") (pintype "passive"))
    )
    (net (code "16") (name "/PWR_PROG_SFP") (class "Default")
      (node (ref "C1030") (pin "2") (pinfunction "2_2") (pintype "passive"))
      (node (ref "IC61") (pin "F14") (pinfunction "TA_PROG_SFP_F14") (pintype "passive"))
      (node (ref "P13") (pin "2") (pinfunction "2_2") (pintype "passive"))
      (node (ref "R541") (pin "2") (pinfunction "2_2") (pintype "passive"))
    )
    (net (code "17") (name "EVVD") (class "Default")
      (node (ref "C1016") (pin "2") (pinfunction "2_2") (pintype "passive"))
      (node (ref "C1017") (pin "1") (pinfunction "1_1") (pintype "passive"))
      (node (ref "IC61") (pin "M8") (pinfunction "EVDD_M8") (pintype "passive"))
      (node (ref "L49") (pin "1") (pinfunction "1_1") (pintype "passive"))
      (node (ref "L50") (pin "1") (pinfunction "1_1") (pintype "passive"))
    )
    (net (code "18") (name "GND") (class "Default")
      (node (ref "C1000") (pin "2") (pinfunction "2_2") (pintype "passive"))
      (node (ref "C1001") (pin "1") (pinfunction "1_1") (pintype "passive"))
      (node (ref "C1002") (pin "1") (pinfunction "1_1") (pintype "passive"))
      (node (ref "C1003") (pin "1") (pinfunction "1_1") (pintype "passive"))
      (node (ref "C1004") (pin "1") (pinfunction "1_1") (pintype "passive"))
      (node (ref "C1005") (pin "1") (pinfunction "1_1") (pintype "passive"))
      (node (ref "C1006") (pin "1") (pinfunction "1_1") (pintype "passive"))
      (node (ref "C1007") (pin "1") (pinfunction "1_1") (pintype "passive"))
      (node (ref "C1008") (pin "1") (pinfunction "1_1") (pintype "passive"))
      (node (ref "C1009") (pin "1") (pinfunction "1_1") (pintype "passive"))
      (node (ref "C1010") (pin "1") (pinfunction "1_1") (pintype "passive"))
      (node (ref "C1011") (pin "1") (pinfunction "1_1") (pintype "passive"))
      (node (ref "C1012") (pin "1") (pinfunction "1_1") (pintype "passive"))
      (node (ref "C1013") (pin "1") (pinfunction "1_1") (pintype "passive"))
      (node (ref "C1014") (pin "1") (pinfunction "1_1") (pintype "passive"))
      (node (ref "C1015") (pin "2") (pinfunction "2_2") (pintype "passive"))
      (node (ref "C1016") (pin "1") (pinfunction "1_1") (pintype "passive"))
      (node (ref "C1017") (pin "2") (pinfunction "2_2") (pintype "passive"))
      (node (ref "C1018") (pin "1") (pinfunction "1_1") (pintype "passive"))
      (node (ref "C1019") (pin "1") (pinfunction "1_1") (pintype "passive"))
      (node (ref "C1020") (pin "1") (pinfunction "1_1") (pintype "passive"))
      (node (ref "C1021") (pin "1") (pinfunction "1_1") (pintype "passive"))
      (node (ref "C1022") (pin "1") (pinfunction "1_1") (pintype "passive"))
      (node (ref "C1023") (pin "1") (pinfunction "1_1") (pintype "passive"))
      (node (ref "C1024") (pin "1") (pinfunction "1_1") (pintype "passive"))
      (node (ref "C1025") (pin "1") (pinfunction "1_1") (pintype "passive"))
      (node (ref "C1026") (pin "1") (pinfunction "1_1") (pintype "passive"))
      (node (ref "C1027") (pin "1") (pinfunction "1_1") (pintype "passive"))
      (node (ref "C1028") (pin "1") (pinfunction "1_1") (pintype "passive"))
      (node (ref "C1029") (pin "1") (pinfunction "1_1") (pintype "passive"))
      (node (ref "C1030") (pin "1") (pinfunction "1_1") (pintype "passive"))
      (node (ref "C1031") (pin "1") (pinfunction "1_1") (pintype "passive"))
      (node (ref "C1032") (pin "2") (pinfunction "2_2") (pintype "passive"))
      (node (ref "C1034") (pin "2") (pinfunction "2_2") (pintype "passive"))
      (node (ref "C1035") (pin "2") (pinfunction "2_2") (pintype "passive"))
      (node (ref "C1036") (pin "1") (pinfunction "1_1") (pintype "passive"))
      (node (ref "C1037") (pin "1") (pinfunction "1_1") (pintype "passive"))
      (node (ref "C1038") (pin "1") (pinfunction "1_1") (pintype "passive"))
      (node (ref "C1042") (pin "1") (pinfunction "1_1") (pintype "passive"))
      (node (ref "C1043") (pin "1") (pinfunction "1_1") (pintype "passive"))
      (node (ref "C1044") (pin "2") (pinfunction "2_2") (pintype "passive"))
      (node (ref "C1045") (pin "2") (pinfunction "2_2") (pintype "passive"))
      (node (ref "C1046") (pin "1") (pinfunction "1_1") (pintype "passive"))
      (node (ref "C1047") (pin "1") (pinfunction "1_1") (pintype "passive"))
      (node (ref "C1048") (pin "1") (pinfunction "1_1") (pintype "passive"))
      (node (ref "C1049") (pin "1") (pinfunction "1_1") (pintype "passive"))
      (node (ref "C1050") (pin "1") (pinfunction "1_1") (pintype "passive"))
      (node (ref "C1051") (pin "1") (pinfunction "1_1") (pintype "passive"))
      (node (ref "C1052") (pin "1") (pinfunction "1_1") (pintype "passive"))
      (node (ref "C1053") (pin "1") (pinfunction "1_1") (pintype "passive"))
      (node (ref "C1054") (pin "2") (pinfunction "2_2") (pintype "passive"))
      (node (ref "C1055") (pin "2") (pinfunction "2_2") (pintype "passive"))
      (node (ref "C1056") (pin "2") (pinfunction "2_2") (pintype "passive"))
      (node (ref "C1057") (pin "2") (pinfunction "2_2") (pintype "passive"))
      (node (ref "C1058") (pin "2") (pinfunction "2_2") (pintype "passive"))
      (node (ref "C1059") (pin "1") (pinfunction "1_1") (pintype "passive"))
      (node (ref "C1060") (pin "1") (pinfunction "1_1") (pintype "passive"))
      (node (ref "C1061") (pin "1") (pinfunction "1_1") (pintype "passive"))
      (node (ref "C1062") (pin "2") (pinfunction "2_2") (pintype "passive"))
      (node (ref "C1063") (pin "2") (pinfunction "2_2") (pintype "passive"))
      (node (ref "C1064") (pin "2") (pinfunction "2_2") (pintype "passive"))
      (node (ref "C1065") (pin "2") (pinfunction "2_2") (pintype "passive"))
      (node (ref "C1066") (pin "1") (pinfunction "1_1") (pintype "passive"))
      (node (ref "C1067") (pin "2") (pinfunction "2_2") (pintype "passive"))
      (node (ref "C1068") (pin "2") (pinfunction "2_2") (pintype "passive"))
      (node (ref "C1069") (pin "2") (pinfunction "2_2") (pintype "passive"))
      (node (ref "C1070") (pin "2") (pinfunction "2_2") (pintype "passive"))
      (node (ref "C1071") (pin "1") (pinfunction "1_1") (pintype "passive"))
      (node (ref "C1072") (pin "2") (pinfunction "2_2") (pintype "passive"))
      (node (ref "C1073") (pin "1") (pinfunction "1_1") (pintype "passive"))
      (node (ref "C1074") (pin "2") (pinfunction "2_2") (pintype "passive"))
      (node (ref "C923") (pin "2") (pinfunction "2_2") (pintype "passive"))
      (node (ref "C924") (pin "2") (pinfunction "2_2") (pintype "passive"))
      (node (ref "C925") (pin "2") (pinfunction "2_2") (pintype "passive"))
      (node (ref "C926") (pin "2") (pinfunction "2_2") (pintype "passive"))
      (node (ref "C927") (pin "2") (pinfunction "2_2") (pintype "passive"))
      (node (ref "C928") (pin "2") (pinfunction "2_2") (pintype "passive"))
      (node (ref "C929") (pin "2") (pinfunction "2_2") (pintype "passive"))
      (node (ref "C930") (pin "2") (pinfunction "2_2") (pintype "passive"))
      (node (ref "C931") (pin "2") (pinfunction "2_2") (pintype "passive"))
      (node (ref "C932") (pin "1") (pinfunction "1_1") (pintype "passive"))
      (node (ref "C933") (pin "1") (pinfunction "1_1") (pintype "passive"))
      (node (ref "C934") (pin "1") (pinfunction "1_1") (pintype "passive"))
      (node (ref "C935") (pin "1") (pinfunction "1_1") (pintype "passive"))
      (node (ref "C936") (pin "1") (pinfunction "1_1") (pintype "passive"))
      (node (ref "C937") (pin "1") (pinfunction "1_1") (pintype "passive"))
      (node (ref "C938") (pin "1") (pinfunction "1_1") (pintype "passive"))
      (node (ref "C939") (pin "1") (pinfunction "1_1") (pintype "passive"))
      (node (ref "C940") (pin "1") (pinfunction "1_1") (pintype "passive"))
      (node (ref "C941") (pin "1") (pinfunction "1_1") (pintype "passive"))
      (node (ref "C942") (pin "2") (pinfunction "2_2") (pintype "passive"))
      (node (ref "C943") (pin "2") (pinfunction "2_2") (pintype "passive"))
      (node (ref "C944") (pin "2") (pinfunction "2_2") (pintype "passive"))
      (node (ref "C945") (pin "1") (pinfunction "1_1") (pintype "passive"))
      (node (ref "C946") (pin "1") (pinfunction "1_1") (pintype "passive"))
      (node (ref "C947") (pin "2") (pinfunction "2_2") (pintype "passive"))
      (node (ref "C948") (pin "1") (pinfunction "1_1") (pintype "passive"))
      (node (ref "C949") (pin "1") (pinfunction "1_1") (pintype "passive"))
      (node (ref "C950") (pin "1") (pinfunction "1_1") (pintype "passive"))
      (node (ref "C951") (pin "1") (pinfunction "1_1") (pintype "passive"))
      (node (ref "C952") (pin "1") (pinfunction "1_1") (pintype "passive"))
      (node (ref "C953") (pin "1") (pinfunction "1_1") (pintype "passive"))
      (node (ref "C954") (pin "1") (pinfunction "1_1") (pintype "passive"))
      (node (ref "C955") (pin "1") (pinfunction "1_1") (pintype "passive"))
      (node (ref "C956") (pin "1") (pinfunction "1_1") (pintype "passive"))
      (node (ref "C957") (pin "1") (pinfunction "1_1") (pintype "passive"))
      (node (ref "C958") (pin "1") (pinfunction "1_1") (pintype "passive"))
      (node (ref "C959") (pin "2") (pinfunction "2_2") (pintype "passive"))
      (node (ref "C960") (pin "2") (pinfunction "2_2") (pintype "passive"))
      (node (ref "C961") (pin "2") (pinfunction "2_2") (pintype "passive"))
      (node (ref "C962") (pin "1") (pinfunction "1_1") (pintype "passive"))
      (node (ref "C963") (pin "1") (pinfunction "1_1") (pintype "passive"))
      (node (ref "C964") (pin "2") (pinfunction "2_2") (pintype "passive"))
      (node (ref "C965") (pin "1") (pinfunction "1_1") (pintype "passive"))
      (node (ref "C966") (pin "1") (pinfunction "1_1") (pintype "passive"))
      (node (ref "C967") (pin "1") (pinfunction "1_1") (pintype "passive"))
      (node (ref "C968") (pin "1") (pinfunction "1_1") (pintype "passive"))
      (node (ref "C969") (pin "1") (pinfunction "1_1") (pintype "passive"))
      (node (ref "C970") (pin "1") (pinfunction "1_1") (pintype "passive"))
      (node (ref "C971") (pin "1") (pinfunction "1_1") (pintype "passive"))
      (node (ref "C972") (pin "1") (pinfunction "1_1") (pintype "passive"))
      (node (ref "C973") (pin "1") (pinfunction "1_1") (pintype "passive"))
      (node (ref "C974") (pin "1") (pinfunction "1_1") (pintype "passive"))
      (node (ref "C975") (pin "1") (pinfunction "1_1") (pintype "passive"))
      (node (ref "C976") (pin "2") (pinfunction "2_2") (pintype "passive"))
      (node (ref "C977") (pin "2") (pinfunction "2_2") (pintype "passive"))
      (node (ref "C978") (pin "2") (pinfunction "2_2") (pintype "passive"))
      (node (ref "C979") (pin "2") (pinfunction "2_2") (pintype "passive"))
      (node (ref "C980") (pin "1") (pinfunction "1_1") (pintype "passive"))
      (node (ref "C981") (pin "1") (pinfunction "1_1") (pintype "passive"))
      (node (ref "C982") (pin "2") (pinfunction "2_2") (pintype "passive"))
      (node (ref "C983") (pin "1") (pinfunction "1_1") (pintype "passive"))
      (node (ref "C984") (pin "1") (pinfunction "1_1") (pintype "passive"))
      (node (ref "C985") (pin "1") (pinfunction "1_1") (pintype "passive"))
      (node (ref "C986") (pin "1") (pinfunction "1_1") (pintype "passive"))
      (node (ref "C987") (pin "1") (pinfunction "1_1") (pintype "passive"))
      (node (ref "C988") (pin "1") (pinfunction "1_1") (pintype "passive"))
      (node (ref "C989") (pin "1") (pinfunction "1_1") (pintype "passive"))
      (node (ref "C990") (pin "2") (pinfunction "2_2") (pintype "passive"))
      (node (ref "C991") (pin "2") (pinfunction "2_2") (pintype "passive"))
      (node (ref "C992") (pin "2") (pinfunction "2_2") (pintype "passive"))
      (node (ref "C993") (pin "2") (pinfunction "2_2") (pintype "passive"))
      (node (ref "C994") (pin "2") (pinfunction "2_2") (pintype "passive"))
      (node (ref "C995") (pin "2") (pinfunction "2_2") (pintype "passive"))
      (node (ref "C996") (pin "2") (pinfunction "2_2") (pintype "passive"))
      (node (ref "C997") (pin "2") (pinfunction "2_2") (pintype "passive"))
      (node (ref "C998") (pin "2") (pinfunction "2_2") (pintype "passive"))
      (node (ref "C999") (pin "2") (pinfunction "2_2") (pintype "passive"))
      (node (ref "IC61") (pin "A2") (pinfunction "GND001_A2") (pintype "passive"))
      (node (ref "IC61") (pin "A24") (pinfunction "GND003_A24") (pintype "passive"))
      (node (ref "IC61") (pin "A5") (pinfunction "GND002_A5") (pintype "passive"))
      (node (ref "IC61") (pin "AB2") (pinfunction "GND135_AB2") (pintype "passive"))
      (node (ref "IC61") (pin "AB4") (pinfunction "GND136_AB4") (pintype "passive"))
      (node (ref "IC61") (pin "AD1") (pinfunction "GND137_AD1") (pintype "passive"))
      (node (ref "IC61") (pin "AD4") (pinfunction "GND138_AD4") (pintype "passive"))
      (node (ref "IC61") (pin "AE2") (pinfunction "GND139_AE2") (pintype "passive"))
      (node (ref "IC61") (pin "B10") (pinfunction "GND007_B10") (pintype "passive"))
      (node (ref "IC61") (pin "B13") (pinfunction "GND008_B13") (pintype "passive"))
      (node (ref "IC61") (pin "B16") (pinfunction "GND009_B16") (pintype "passive"))
      (node (ref "IC61") (pin "B19") (pinfunction "GND010_B19") (pintype "passive"))
      (node (ref "IC61") (pin "B21") (pinfunction "GND011_B21") (pintype "passive"))
      (node (ref "IC61") (pin "B25") (pinfunction "GND012_B25") (pintype "passive"))
      (node (ref "IC61") (pin "B3") (pinfunction "GND004_B3") (pintype "passive"))
      (node (ref "IC61") (pin "B4") (pinfunction "GND005_B4") (pintype "passive"))
      (node (ref "IC61") (pin "B7") (pinfunction "GND006_B7") (pintype "passive"))
      (node (ref "IC61") (pin "C1") (pinfunction "GND013_C1") (pintype "passive"))
      (node (ref "IC61") (pin "C2") (pinfunction "GND014_C2") (pintype "passive"))
      (node (ref "IC61") (pin "C23") (pinfunction "GND016_C23") (pintype "passive"))
      (node (ref "IC61") (pin "C5") (pinfunction "GND015_C5") (pintype "passive"))
      (node (ref "IC61") (pin "D12") (pinfunction "GND021_D12") (pintype "passive"))
      (node (ref "IC61") (pin "D15") (pinfunction "GND022_D15") (pintype "passive"))
      (node (ref "IC61") (pin "D18") (pinfunction "GND023_D18") (pintype "passive"))
      (node (ref "IC61") (pin "D21") (pinfunction "GND024_D21") (pintype "passive"))
      (node (ref "IC61") (pin "D3") (pinfunction "GND017_D3") (pintype "passive"))
      (node (ref "IC61") (pin "D4") (pinfunction "GND018_D4") (pintype "passive"))
      (node (ref "IC61") (pin "D7") (pinfunction "GND019_D7") (pintype "passive"))
      (node (ref "IC61") (pin "D9") (pinfunction "GND020_D9") (pintype "passive"))
      (node (ref "IC61") (pin "E1") (pinfunction "GND025_E1") (pintype "passive"))
      (node (ref "IC61") (pin "E2") (pinfunction "GND026_E2") (pintype "passive"))
      (node (ref "IC61") (pin "E22") (pinfunction "GND028_E22") (pintype "passive"))
      (node (ref "IC61") (pin "E24") (pinfunction "GND029_E24") (pintype "passive"))
      (node (ref "IC61") (pin "E5") (pinfunction "GND027_E5") (pintype "passive"))
      (node (ref "IC61") (pin "F11") (pinfunction "GND034_F11") (pintype "passive"))
      (node (ref "IC61") (pin "F12") (pinfunction "GND035_F12") (pintype "passive"))
      (node (ref "IC61") (pin "F13") (pinfunction "GND036_F13") (pintype "passive"))
      (node (ref "IC61") (pin "F17") (pinfunction "GND037_F17") (pintype "passive"))
      (node (ref "IC61") (pin "F20") (pinfunction "GND038_F20") (pintype "passive"))
      (node (ref "IC61") (pin "F3") (pinfunction "GND030_F3") (pintype "passive"))
      (node (ref "IC61") (pin "F4") (pinfunction "GND031_F4") (pintype "passive"))
      (node (ref "IC61") (pin "F7") (pinfunction "GND032_F7") (pintype "passive"))
      (node (ref "IC61") (pin "F8") (pinfunction "GND033_F8") (pintype "passive"))
      (node (ref "IC61") (pin "G1") (pinfunction "GND039_G1") (pintype "passive"))
      (node (ref "IC61") (pin "G2") (pinfunction "GND040_G2") (pintype "passive"))
      (node (ref "IC61") (pin "G22") (pinfunction "GND041_G22") (pintype "passive"))
      (node (ref "IC61") (pin "G24") (pinfunction "GND042_G24") (pintype "passive"))
      (node (ref "IC61") (pin "H10") (pinfunction "GND048_H10") (pintype "passive"))
      (node (ref "IC61") (pin "H11") (pinfunction "GND049_H11") (pintype "passive"))
      (node (ref "IC61") (pin "H12") (pinfunction "GND050_H12") (pintype "passive"))
      (node (ref "IC61") (pin "H13") (pinfunction "GND051_H13") (pintype "passive"))
      (node (ref "IC61") (pin "H14") (pinfunction "GND052_H14") (pintype "passive"))
      (node (ref "IC61") (pin "H15") (pinfunction "GND053_H15") (pintype "passive"))
      (node (ref "IC61") (pin "H16") (pinfunction "GND054_H16") (pintype "passive"))
      (node (ref "IC61") (pin "H17") (pinfunction "GND055_H17") (pintype "passive"))
      (node (ref "IC61") (pin "H3") (pinfunction "GND043_H3") (pintype "passive"))
      (node (ref "IC61") (pin "H4") (pinfunction "GND044_H4") (pintype "passive"))
      (node (ref "IC61") (pin "H5") (pinfunction "GND045_H5") (pintype "passive"))
      (node (ref "IC61") (pin "H8") (pinfunction "GND046_H8") (pintype "passive"))
      (node (ref "IC61") (pin "H9") (pinfunction "GND047_H9") (pintype "passive"))
      (node (ref "IC61") (pin "J19") (pinfunction "GND057_J19") (pintype "passive"))
      (node (ref "IC61") (pin "J20") (pinfunction "GND058_J20") (pintype "passive"))
      (node (ref "IC61") (pin "J24") (pinfunction "GND059_J24") (pintype "passive"))
      (node (ref "IC61") (pin "J7") (pinfunction "GND056_J7") (pintype "passive"))
      (node (ref "IC61") (pin "K10") (pinfunction "GND063_K10") (pintype "passive"))
      (node (ref "IC61") (pin "K12") (pinfunction "GND064_K12") (pintype "passive"))
      (node (ref "IC61") (pin "K14") (pinfunction "GND065_K14") (pintype "passive"))
      (node (ref "IC61") (pin "K16") (pinfunction "GND066_K16") (pintype "passive"))
      (node (ref "IC61") (pin "K19") (pinfunction "GND067_K19") (pintype "passive"))
      (node (ref "IC61") (pin "K2") (pinfunction "GND060_K2") (pintype "passive"))
      (node (ref "IC61") (pin "K22") (pinfunction "GND068_K22") (pintype "passive"))
      (node (ref "IC61") (pin "K4") (pinfunction "GND061_K4") (pintype "passive"))
      (node (ref "IC61") (pin "K7") (pinfunction "GND062_K7") (pintype "passive"))
      (node (ref "IC61") (pin "L11") (pinfunction "GND071_L11") (pintype "passive"))
      (node (ref "IC61") (pin "L13") (pinfunction "GND072_L13") (pintype "passive"))
      (node (ref "IC61") (pin "L15") (pinfunction "GND073_L15") (pintype "passive"))
      (node (ref "IC61") (pin "L17") (pinfunction "GND074_L17") (pintype "passive"))
      (node (ref "IC61") (pin "L19") (pinfunction "GND075_L19") (pintype "passive"))
      (node (ref "IC61") (pin "L7") (pinfunction "GND069_L7") (pintype "passive"))
      (node (ref "IC61") (pin "L9") (pinfunction "GND070_L9") (pintype "passive"))
      (node (ref "IC61") (pin "P10") (pinfunction "GND097_P10") (pintype "passive"))
      (node (ref "IC61") (pin "P12") (pinfunction "GND098_P12") (pintype "passive"))
      (node (ref "IC61") (pin "P14") (pinfunction "GND099_P14") (pintype "passive"))
      (node (ref "IC61") (pin "P16") (pinfunction "GND100_P16") (pintype "passive"))
      (node (ref "IC61") (pin "P19") (pinfunction "GND101_P19") (pintype "passive"))
      (node (ref "IC61") (pin "P22") (pinfunction "GND102_P22") (pintype "passive"))
      (node (ref "IC61") (pin "P24") (pinfunction "GND103_P24") (pintype "passive"))
      (node (ref "IC61") (pin "P8") (pinfunction "GND096_P8") (pintype "passive"))
      (node (ref "IC61") (pin "R11") (pinfunction "GND105_R11") (pintype "passive"))
      (node (ref "IC61") (pin "R13") (pinfunction "GND106_R13") (pintype "passive"))
      (node (ref "IC61") (pin "R15") (pinfunction "GND107_R15") (pintype "passive"))
      (node (ref "IC61") (pin "R17") (pinfunction "GND108_R17") (pintype "passive"))
      (node (ref "IC61") (pin "R19") (pinfunction "GND109_R19") (pintype "passive"))
      (node (ref "IC61") (pin "R25") (pinfunction "GND110_R25") (pintype "passive"))
      (node (ref "IC61") (pin "R9") (pinfunction "GND104_R9") (pintype "passive"))
      (node (ref "IC61") (pin "T10") (pinfunction "GND114_T10") (pintype "passive"))
      (node (ref "IC61") (pin "T12") (pinfunction "GND115_T12") (pintype "passive"))
      (node (ref "IC61") (pin "T14") (pinfunction "GND116_T14") (pintype "passive"))
      (node (ref "IC61") (pin "T2") (pinfunction "GND111_T2") (pintype "passive"))
      (node (ref "IC61") (pin "T20") (pinfunction "GND117_T20") (pintype "passive"))
      (node (ref "IC61") (pin "T4") (pinfunction "GND112_T4") (pintype "passive"))
      (node (ref "IC61") (pin "T8") (pinfunction "GND113_T8") (pintype "passive"))
      (node (ref "IC61") (pin "U11") (pinfunction "GND120_U11") (pintype "passive"))
      (node (ref "IC61") (pin "U20") (pinfunction "GND121_U20") (pintype "passive"))
      (node (ref "IC61") (pin "U6") (pinfunction "GND118_U6") (pintype "passive"))
      (node (ref "IC61") (pin "U9") (pinfunction "GND119_U9") (pintype "passive"))
      (node (ref "IC61") (pin "V10") (pinfunction "GND125_V10") (pintype "passive"))
      (node (ref "IC61") (pin "V11") (pinfunction "GND126_V11") (pintype "passive"))
      (node (ref "IC61") (pin "V12") (pinfunction "GND127_V12") (pintype "passive"))
      (node (ref "IC61") (pin "V13") (pinfunction "GND128_V13") (pintype "passive"))
      (node (ref "IC61") (pin "V14") (pinfunction "GND129_V14") (pintype "passive"))
      (node (ref "IC61") (pin "V2") (pinfunction "GND122_V2") (pintype "passive"))
      (node (ref "IC61") (pin "V20") (pinfunction "GND130_V20") (pintype "passive"))
      (node (ref "IC61") (pin "V8") (pinfunction "GND123_V8") (pintype "passive"))
      (node (ref "IC61") (pin "V9") (pinfunction "GND124_V9") (pintype "passive"))
      (node (ref "IC61") (pin "W20") (pinfunction "GND132_W20") (pintype "passive"))
      (node (ref "IC61") (pin "W4") (pinfunction "GND131_W4") (pintype "passive"))
      (node (ref "IC61") (pin "Y2") (pinfunction "GND133_Y2") (pintype "passive"))
      (node (ref "IC61") (pin "Y20") (pinfunction "GND134_Y20") (pintype "passive"))
      (node (ref "R538") (pin "1") (pinfunction "1_1") (pintype "passive"))
      (node (ref "R539") (pin "1") (pinfunction "1_1") (pintype "passive"))
      (node (ref "R540") (pin "1") (pinfunction "1_1") (pintype "passive"))
      (node (ref "R541") (pin "1") (pinfunction "1_1") (pintype "passive"))
    )
    (net (code "19") (name "Net-(C919-Pad1)") (class "Default")
      (node (ref "C919") (pin "1") (pinfunction "1_1") (pintype "passive"))
      (node (ref "C920") (pin "1") (pinfunction "1_1") (pintype "passive"))
      (node (ref "C921") (pin "2") (pinfunction "2_2") (pintype "passive"))
      (node (ref "C922") (pin "1") (pinfunction "1_1") (pintype "passive"))
    )
    (net (code "20") (name "Net-(C1033-Pad1)") (class "Default")
      (node (ref "C1033") (pin "1") (pinfunction "1_1") (pintype "passive"))
      (node (ref "C1041") (pin "1") (pinfunction "1_1") (pintype "passive"))
      (node (ref "R542") (pin "1") (pinfunction "1_1") (pintype "passive"))
    )
    (net (code "21") (name "Net-(C1039-Pad1)") (class "Default")
      (node (ref "C1039") (pin "1") (pinfunction "1_1") (pintype "passive"))
      (node (ref "C1040") (pin "2") (pinfunction "2_2") (pintype "passive"))
    )
    (net (code "22") (name "Net-(IC61G-LVDD2)") (class "Default")
      (node (ref "C1034") (pin "1") (pinfunction "1_1") (pintype "passive"))
      (node (ref "C1035") (pin "1") (pinfunction "1_1") (pintype "passive"))
      (node (ref "C1036") (pin "2") (pinfunction "2_2") (pintype "passive"))
      (node (ref "C1037") (pin "2") (pinfunction "2_2") (pintype "passive"))
      (node (ref "C1038") (pin "2") (pinfunction "2_2") (pintype "passive"))
      (node (ref "IC61") (pin "U13") (pinfunction "LVDD2_U13") (pintype "passive"))
      (node (ref "IC61") (pin "U14") (pinfunction "LVDD3_U14") (pintype "passive"))
      (node (ref "L51") (pin "2") (pinfunction "2_2") (pintype "passive"))
    )
    (net (code "23") (name "Net-(IC61H-SENSEGND)") (class "Default")
      (node (ref "IC61") (pin "V7") (pinfunction "SENSEGND_V7") (pintype "passive"))
      (node (ref "R537") (pin "1") (pinfunction "1_1") (pintype "passive"))
    )
    (net (code "24") (name "Net-(IC61H-SENSEVDD)") (class "Default")
      (node (ref "IC61") (pin "W7") (pinfunction "SENSEVDD_W7") (pintype "passive"))
      (node (ref "R536") (pin "1") (pinfunction "1_1") (pintype "passive"))
    )
    (net (code "25") (name "Net-(IC61H-TVDD)") (class "Default")
      (node (ref "C981") (pin "2") (pinfunction "2_2") (pintype "passive"))
      (node (ref "C982") (pin "1") (pinfunction "1_1") (pintype "passive"))
      (node (ref "IC61") (pin "V6") (pinfunction "TVDD_V6") (pintype "passive"))
      (node (ref "L48") (pin "1") (pinfunction "1_1") (pintype "passive"))
    )
    (net (code "26") (name "PWR_X1VDD") (class "Default")
      (node (ref "C1056") (pin "1") (pinfunction "1_1") (pintype "passive"))
      (node (ref "C1057") (pin "1") (pinfunction "1_1") (pintype "passive"))
      (node (ref "C1058") (pin "1") (pinfunction "1_1") (pintype "passive"))
      (node (ref "L53") (pin "2") (pinfunction "2_2") (pintype "passive"))
      (node (ref "L55") (pin "2") (pinfunction "2_2") (pintype "passive"))
    )
    (net (code "27") (name "S1VDD") (class "Default")
      (node (ref "C1042") (pin "2") (pinfunction "2_2") (pintype "passive"))
      (node (ref "C1043") (pin "2") (pinfunction "2_2") (pintype "passive"))
      (node (ref "C1044") (pin "1") (pinfunction "1_1") (pintype "passive"))
      (node (ref "C1045") (pin "1") (pinfunction "1_1") (pintype "passive"))
      (node (ref "C1046") (pin "2") (pinfunction "2_2") (pintype "passive"))
      (node (ref "C1047") (pin "2") (pinfunction "2_2") (pintype "passive"))
      (node (ref "C1048") (pin "2") (pinfunction "2_2") (pintype "passive"))
      (node (ref "C1049") (pin "2") (pinfunction "2_2") (pintype "passive"))
      (node (ref "IC61") (pin "T15") (pinfunction "S1VDD1_T15") (pintype "passive"))
      (node (ref "IC61") (pin "T16") (pinfunction "S1VDD2_T16") (pintype "passive"))
      (node (ref "IC61") (pin "T17") (pinfunction "S1VDD3_T17") (pintype "passive"))
      (node (ref "IC61") (pin "T18") (pinfunction "S1VDD4_T18") (pintype "passive"))
      (node (ref "L52") (pin "2") (pinfunction "2_2") (pintype "passive"))
      (node (ref "L54") (pin "2") (pinfunction "2_2") (pintype "passive"))
      (node (ref "L56") (pin "2") (pinfunction "2_2") (pintype "passive"))
      (node (ref "L57") (pin "2") (pinfunction "2_2") (pintype "passive"))
    )
    (net (code "28") (name "S1VDD_SRC") (class "Default")
      (node (ref "L56") (pin "1") (pinfunction "1_1") (pintype "passive"))
      (node (ref "L57") (pin "1") (pinfunction "1_1") (pintype "passive"))
    )
    (net (code "29") (name "VDD_FA_VDD") (class "Default")
      (node (ref "C1033") (pin "2") (pinfunction "2_2") (pintype "passive"))
      (node (ref "C1041") (pin "2") (pinfunction "2_2") (pintype "passive"))
      (node (ref "P15") (pin "1") (pinfunction "1_1") (pintype "passive"))
      (node (ref "R542") (pin "2") (pinfunction "2_2") (pintype "passive"))
    )
    (net (code "30") (name "VDD_LP") (class "Default")
      (node (ref "C979") (pin "1") (pinfunction "1_1") (pintype "passive"))
      (node (ref "C980") (pin "2") (pinfunction "2_2") (pintype "passive"))
      (node (ref "IC61") (pin "H20") (pinfunction "TA_BB_VDD_H20") (pintype "passive"))
      (node (ref "P12") (pin "1") (pinfunction "1_1") (pintype "passive"))
      (node (ref "R538") (pin "2") (pinfunction "2_2") (pintype "passive"))
    )
    (net (code "31") (name "VDD_USB_HVVD") (class "Default")
      (node (ref "C962") (pin "2") (pinfunction "2_2") (pintype "passive"))
      (node (ref "C963") (pin "2") (pinfunction "2_2") (pintype "passive"))
      (node (ref "C964") (pin "1") (pinfunction "1_1") (pintype "passive"))
      (node (ref "C965") (pin "2") (pinfunction "2_2") (pintype "passive"))
      (node (ref "IC61") (pin "J8") (pinfunction "USB_HVDD1_J8") (pintype "passive"))
      (node (ref "IC61") (pin "J9") (pinfunction "USB_HVDD2_J9") (pintype "passive"))
      (node (ref "L47") (pin "1") (pinfunction "1_1") (pintype "passive"))
    )
    (net (code "32") (name "VDD_USB_SDVDD") (class "Default")
      (node (ref "C945") (pin "2") (pinfunction "2_2") (pintype "passive"))
      (node (ref "C946") (pin "2") (pinfunction "2_2") (pintype "passive"))
      (node (ref "C947") (pin "1") (pinfunction "1_1") (pintype "passive"))
      (node (ref "C948") (pin "2") (pinfunction "2_2") (pintype "passive"))
      (node (ref "IC61") (pin "K11") (pinfunction "USB_SDVDD2_K11") (pintype "passive"))
      (node (ref "IC61") (pin "K9") (pinfunction "USB_SDVDD1_K9") (pintype "passive"))
      (node (ref "L46") (pin "1") (pinfunction "1_1") (pintype "passive"))
    )
    (net (code "33") (name "VDD_USB_SVDD") (class "Default")
      (node (ref "C919") (pin "2") (pinfunction "2_2") (pintype "passive"))
      (node (ref "C920") (pin "2") (pinfunction "2_2") (pintype "passive"))
      (node (ref "C921") (pin "1") (pinfunction "1_1") (pintype "passive"))
      (node (ref "C922") (pin "2") (pinfunction "2_2") (pintype "passive"))
      (node (ref "IC61") (pin "J10") (pinfunction "USB_SVDD1_J10") (pintype "passive"))
      (node (ref "IC61") (pin "J11") (pinfunction "USB_SVDD2_J11") (pintype "passive"))
      (node (ref "L45") (pin "1") (pinfunction "1_1") (pintype "passive"))
    )
    (net (code "34") (name "X1VDD") (class "Default")
      (node (ref "C1050") (pin "2") (pinfunction "2_2") (pintype "passive"))
      (node (ref "C1051") (pin "2") (pinfunction "2_2") (pintype "passive"))
      (node (ref "C1052") (pin "2") (pinfunction "2_2") (pintype "passive"))
      (node (ref "C1053") (pin "2") (pinfunction "2_2") (pintype "passive"))
      (node (ref "C1054") (pin "1") (pinfunction "1_1") (pintype "passive"))
      (node (ref "C1055") (pin "1") (pinfunction "1_1") (pintype "passive"))
      (node (ref "C1059") (pin "2") (pinfunction "2_2") (pintype "passive"))
      (node (ref "C1060") (pin "2") (pinfunction "2_2") (pintype "passive"))
      (node (ref "IC61") (pin "W15") (pinfunction "X1VDD1_W15") (pintype "passive"))
      (node (ref "IC61") (pin "W16") (pinfunction "X1VDD2_W16") (pintype "passive"))
      (node (ref "IC61") (pin "W17") (pinfunction "X1VDD3_W17") (pintype "passive"))
      (node (ref "IC61") (pin "W18") (pinfunction "X1VDD4_W18") (pintype "passive"))
      (node (ref "IC61") (pin "Y19") (pinfunction "X1VDD5_Y19") (pintype "passive"))
      (node (ref "L53") (pin "1") (pinfunction "1_1") (pintype "passive"))
      (node (ref "L55") (pin "1") (pinfunction "1_1") (pintype "passive"))
      (node (ref "R545") (pin "1") (pinfunction "1_1") (pintype "passive"))
      (node (ref "R546") (pin "1") (pinfunction "1_1") (pintype "passive"))
    )
    (net (code "35") (name "unconnected-(IC61G-FA_VL-PadR7)") (class "Default")
      (node (ref "IC61") (pin "R7") (pinfunction "FA_VL_R7") (pintype "passive"))
    )
    (net (code "36") (name "unconnected-(IC61G-LVDD1-PadU12)") (class "Default")
      (node (ref "IC61") (pin "U12") (pinfunction "LVDD1_U12") (pintype "passive"))
    )
    (net (code "37") (name "unconnected-(IC61G-TH_TPA-PadP5)") (class "Default")
      (node (ref "IC61") (pin "P5") (pinfunction "TH_TPA_P5") (pintype "passive+no_connect"))
    )
    (net (code "38") (name "unconnected-(IC61I-S1VDD5-PadW14)") (class "Default")
      (node (ref "IC61") (pin "W14") (pinfunction "S1VDD5_W14") (pintype "passive"))
    )
    (net (code "39") (name "unconnected-(IC61J-GND076-PadL20)") (class "Default")
      (node (ref "IC61") (pin "L20") (pinfunction "GND076_L20") (pintype "passive"))
    )
    (net (code "40") (name "unconnected-(IC61J-GND077-PadL24)") (class "Default")
      (node (ref "IC61") (pin "L24") (pinfunction "GND077_L24") (pintype "passive"))
    )
    (net (code "41") (name "unconnected-(IC61J-GND078-PadM7)") (class "Default")
      (node (ref "IC61") (pin "M7") (pinfunction "GND078_M7") (pintype "passive"))
    )
    (net (code "42") (name "unconnected-(IC61J-GND079-PadM10)") (class "Default")
      (node (ref "IC61") (pin "M10") (pinfunction "GND079_M10") (pintype "passive"))
    )
    (net (code "43") (name "unconnected-(IC61J-GND080-PadM12)") (class "Default")
      (node (ref "IC61") (pin "M12") (pinfunction "GND080_M12") (pintype "passive"))
    )
    (net (code "44") (name "unconnected-(IC61J-GND081-PadM14)") (class "Default")
      (node (ref "IC61") (pin "M14") (pinfunction "GND081_M14") (pintype "passive"))
    )
    (net (code "45") (name "unconnected-(IC61J-GND082-PadM16)") (class "Default")
      (node (ref "IC61") (pin "M16") (pinfunction "GND082_M16") (pintype "passive"))
    )
    (net (code "46") (name "unconnected-(IC61J-GND083-PadM19)") (class "Default")
      (node (ref "IC61") (pin "M19") (pinfunction "GND083_M19") (pintype "passive"))
    )
    (net (code "47") (name "unconnected-(IC61J-GND084-PadM22)") (class "Default")
      (node (ref "IC61") (pin "M22") (pinfunction "GND084_M22") (pintype "passive"))
    )
    (net (code "48") (name "unconnected-(IC61J-GND085-PadN2)") (class "Default")
      (node (ref "IC61") (pin "N2") (pinfunction "GND085_N2") (pintype "passive"))
    )
    (net (code "49") (name "unconnected-(IC61J-GND086-PadN4)") (class "Default")
      (node (ref "IC61") (pin "N4") (pinfunction "GND086_N4") (pintype "passive"))
    )
    (net (code "50") (name "unconnected-(IC61J-GND087-PadN6)") (class "Default")
      (node (ref "IC61") (pin "N6") (pinfunction "GND087_N6") (pintype "passive"))
    )
    (net (code "51") (name "unconnected-(IC61J-GND088-PadN9)") (class "Default")
      (node (ref "IC61") (pin "N9") (pinfunction "GND088_N9") (pintype "passive"))
    )
    (net (code "52") (name "unconnected-(IC61J-GND089-PadN11)") (class "Default")
      (node (ref "IC61") (pin "N11") (pinfunction "GND089_N11") (pintype "passive"))
    )
    (net (code "53") (name "unconnected-(IC61J-GND090-PadN13)") (class "Default")
      (node (ref "IC61") (pin "N13") (pinfunction "GND090_N13") (pintype "passive"))
    )
    (net (code "54") (name "unconnected-(IC61J-GND091-PadN15)") (class "Default")
      (node (ref "IC61") (pin "N15") (pinfunction "GND091_N15") (pintype "passive"))
    )
    (net (code "55") (name "unconnected-(IC61J-GND092-PadN17)") (class "Default")
      (node (ref "IC61") (pin "N17") (pinfunction "GND092_N17") (pintype "passive"))
    )
    (net (code "56") (name "unconnected-(IC61J-GND093-PadN19)") (class "Default")
      (node (ref "IC61") (pin "N19") (pinfunction "GND093_N19") (pintype "passive"))
    )
    (net (code "57") (name "unconnected-(IC61J-GND094-PadN20)") (class "Default")
      (node (ref "IC61") (pin "N20") (pinfunction "GND094_N20") (pintype "passive"))
    )
    (net (code "58") (name "unconnected-(IC61J-GND095-PadP7)") (class "Default")
      (node (ref "IC61") (pin "P7") (pinfunction "GND095_P7") (pintype "passive"))
    )
    (net (code "59") (name "unconnected-(IC61M-NC-PadAA5)") (class "Default")
      (node (ref "IC61") (pin "AA5") (pinfunction "NC_AA5") (pintype "passive"))
    )
    (net (code "60") (name "unconnected-(IC61M-NC-PadAA6)") (class "Default")
      (node (ref "IC61") (pin "AA6") (pinfunction "NC_AA6") (pintype "passive"))
    )
    (net (code "61") (name "unconnected-(IC61M-NC-PadAA7)") (class "Default")
      (node (ref "IC61") (pin "AA7") (pinfunction "NC_AA7") (pintype "passive"))
    )
    (net (code "62") (name "unconnected-(IC61M-NC-PadAA8)") (class "Default")
      (node (ref "IC61") (pin "AA8") (pinfunction "NC_AA8") (pintype "passive"))
    )
    (net (code "63") (name "unconnected-(IC61M-NC-PadAA9)") (class "Default")
      (node (ref "IC61") (pin "AA9") (pinfunction "NC_AA9") (pintype "passive"))
    )
    (net (code "64") (name "unconnected-(IC61M-NC-PadAA10)") (class "Default")
      (node (ref "IC61") (pin "AA10") (pinfunction "NC_AA10") (pintype "passive"))
    )
    (net (code "65") (name "unconnected-(IC61M-NC-PadAA11)") (class "Default")
      (node (ref "IC61") (pin "AA11") (pinfunction "NC_AA11") (pintype "passive"))
    )
    (net (code "66") (name "unconnected-(IC61M-NC-PadAA12)") (class "Default")
      (node (ref "IC61") (pin "AA12") (pinfunction "NC_AA12") (pintype "passive"))
    )
    (net (code "67") (name "unconnected-(IC61M-NC-PadAB5)") (class "Default")
      (node (ref "IC61") (pin "AB5") (pinfunction "NC_AB5") (pintype "passive"))
    )
    (net (code "68") (name "unconnected-(IC61M-NC-PadAB6)") (class "Default")
      (node (ref "IC61") (pin "AB6") (pinfunction "NC_AB6") (pintype "passive"))
    )
    (net (code "69") (name "unconnected-(IC61M-NC-PadAB7)") (class "Default")
      (node (ref "IC61") (pin "AB7") (pinfunction "NC_AB7") (pintype "passive"))
    )
    (net (code "70") (name "unconnected-(IC61M-NC-PadAB8)") (class "Default")
      (node (ref "IC61") (pin "AB8") (pinfunction "NC_AB8") (pintype "passive"))
    )
    (net (code "71") (name "unconnected-(IC61M-NC-PadAB9)") (class "Default")
      (node (ref "IC61") (pin "AB9") (pinfunction "NC_AB9") (pintype "passive"))
    )
    (net (code "72") (name "unconnected-(IC61M-NC-PadAB10)") (class "Default")
      (node (ref "IC61") (pin "AB10") (pinfunction "NC_AB10") (pintype "passive"))
    )
    (net (code "73") (name "unconnected-(IC61M-NC-PadAB11)") (class "Default")
      (node (ref "IC61") (pin "AB11") (pinfunction "NC_AB11") (pintype "passive"))
    )
    (net (code "74") (name "unconnected-(IC61M-NC-PadAB12)") (class "Default")
      (node (ref "IC61") (pin "AB12") (pinfunction "NC_AB12") (pintype "passive"))
    )
    (net (code "75") (name "unconnected-(IC61M-NC-PadAC5)") (class "Default")
      (node (ref "IC61") (pin "AC5") (pinfunction "NC_AC5") (pintype "passive"))
    )
    (net (code "76") (name "unconnected-(IC61M-NC-PadAC6)") (class "Default")
      (node (ref "IC61") (pin "AC6") (pinfunction "NC_AC6") (pintype "passive"))
    )
    (net (code "77") (name "unconnected-(IC61M-NC-PadAC7)") (class "Default")
      (node (ref "IC61") (pin "AC7") (pinfunction "NC_AC7") (pintype "passive"))
    )
    (net (code "78") (name "unconnected-(IC61M-NC-PadAC8)") (class "Default")
      (node (ref "IC61") (pin "AC8") (pinfunction "NC_AC8") (pintype "passive"))
    )
    (net (code "79") (name "unconnected-(IC61M-NC-PadAC9)") (class "Default")
      (node (ref "IC61") (pin "AC9") (pinfunction "NC_AC9") (pintype "passive"))
    )
    (net (code "80") (name "unconnected-(IC61M-NC-PadAC10)") (class "Default")
      (node (ref "IC61") (pin "AC10") (pinfunction "NC_AC10") (pintype "passive"))
    )
    (net (code "81") (name "unconnected-(IC61M-NC-PadAC11)") (class "Default")
      (node (ref "IC61") (pin "AC11") (pinfunction "NC_AC11") (pintype "passive"))
    )
    (net (code "82") (name "unconnected-(IC61M-NC-PadAC12)") (class "Default")
      (node (ref "IC61") (pin "AC12") (pinfunction "NC_AC12") (pintype "passive"))
    )
    (net (code "83") (name "unconnected-(IC61M-NC-PadAD5)") (class "Default")
      (node (ref "IC61") (pin "AD5") (pinfunction "NC_AD5") (pintype "passive"))
    )
    (net (code "84") (name "unconnected-(IC61M-NC-PadAD6)") (class "Default")
      (node (ref "IC61") (pin "AD6") (pinfunction "NC_AD6") (pintype "passive+no_connect"))
    )
    (net (code "85") (name "unconnected-(IC61M-NC-PadAD7)") (class "Default")
      (node (ref "IC61") (pin "AD7") (pinfunction "NC_AD7") (pintype "passive+no_connect"))
    )
    (net (code "86") (name "unconnected-(IC61M-NC-PadAD8)") (class "Default")
      (node (ref "IC61") (pin "AD8") (pinfunction "NC_AD8") (pintype "passive+no_connect"))
    )
    (net (code "87") (name "unconnected-(IC61M-NC-PadAD9)") (class "Default")
      (node (ref "IC61") (pin "AD9") (pinfunction "NC_AD9") (pintype "passive+no_connect"))
    )
    (net (code "88") (name "unconnected-(IC61M-NC-PadAD10)") (class "Default")
      (node (ref "IC61") (pin "AD10") (pinfunction "NC_AD10") (pintype "passive"))
    )
    (net (code "89") (name "unconnected-(IC61M-NC-PadAD11)") (class "Default")
      (node (ref "IC61") (pin "AD11") (pinfunction "NC_AD11") (pintype "passive"))
    )
    (net (code "90") (name "unconnected-(IC61M-NC-PadAD12)") (class "Default")
      (node (ref "IC61") (pin "AD12") (pinfunction "NC_AD12") (pintype "passive"))
    )
    (net (code "91") (name "unconnected-(IC61M-NC-PadAE5)") (class "Default")
      (node (ref "IC61") (pin "AE5") (pinfunction "NC_AE5") (pintype "passive+no_connect"))
    )
    (net (code "92") (name "unconnected-(IC61M-NC-PadAE6)") (class "Default")
      (node (ref "IC61") (pin "AE6") (pinfunction "NC_AE6") (pintype "passive+no_connect"))
    )
    (net (code "93") (name "unconnected-(IC61M-NC-PadAE7)") (class "Default")
      (node (ref "IC61") (pin "AE7") (pinfunction "NC_AE7") (pintype "passive+no_connect"))
    )
    (net (code "94") (name "unconnected-(IC61M-NC-PadAE8)") (class "Default")
      (node (ref "IC61") (pin "AE8") (pinfunction "NC_AE8") (pintype "passive+no_connect"))
    )
    (net (code "95") (name "unconnected-(IC61M-NC-PadAE9)") (class "Default")
      (node (ref "IC61") (pin "AE9") (pinfunction "NC_AE9") (pintype "passive+no_connect"))
    )
    (net (code "96") (name "unconnected-(IC61M-NC-PadAE10)") (class "Default")
      (node (ref "IC61") (pin "AE10") (pinfunction "NC_AE10") (pintype "passive+no_connect"))
    )
    (net (code "97") (name "unconnected-(IC61M-NC-PadAE11)") (class "Default")
      (node (ref "IC61") (pin "AE11") (pinfunction "NC_AE11") (pintype "passive+no_connect"))
    )
    (net (code "98") (name "unconnected-(IC61M-NC-PadAE12)") (class "Default")
      (node (ref "IC61") (pin "AE12") (pinfunction "NC_AE12") (pintype "passive+no_connect"))
    )
    (net (code "99") (name "unconnected-(IC61M-NC-PadK6)") (class "Default")
      (node (ref "IC61") (pin "K6") (pinfunction "NC_K6") (pintype "passive+no_connect"))
    )
    (net (code "100") (name "unconnected-(IC61M-NC-PadL6)") (class "Default")
      (node (ref "IC61") (pin "L6") (pinfunction "NC_L6") (pintype "passive+no_connect"))
    )
    (net (code "101") (name "unconnected-(IC61M-NC-PadM6)") (class "Default")
      (node (ref "IC61") (pin "M6") (pinfunction "NC_M6") (pintype "passive+no_connect"))
    )
    (net (code "102") (name "unconnected-(IC61M-NC-PadY7)") (class "Default")
      (node (ref "IC61") (pin "Y7") (pinfunction "NC_Y7") (pintype "passive+no_connect"))
    )
    (net (code "103") (name "unconnected-(IC61M-NC-PadY13)") (class "Default")
      (node (ref "IC61") (pin "Y13") (pinfunction "NC_Y13") (pintype "passive+no_connect"))
    )
  )
)
